# Sheet_TCU.net
KiCad netlist of a schematic drawn in Altium Designer
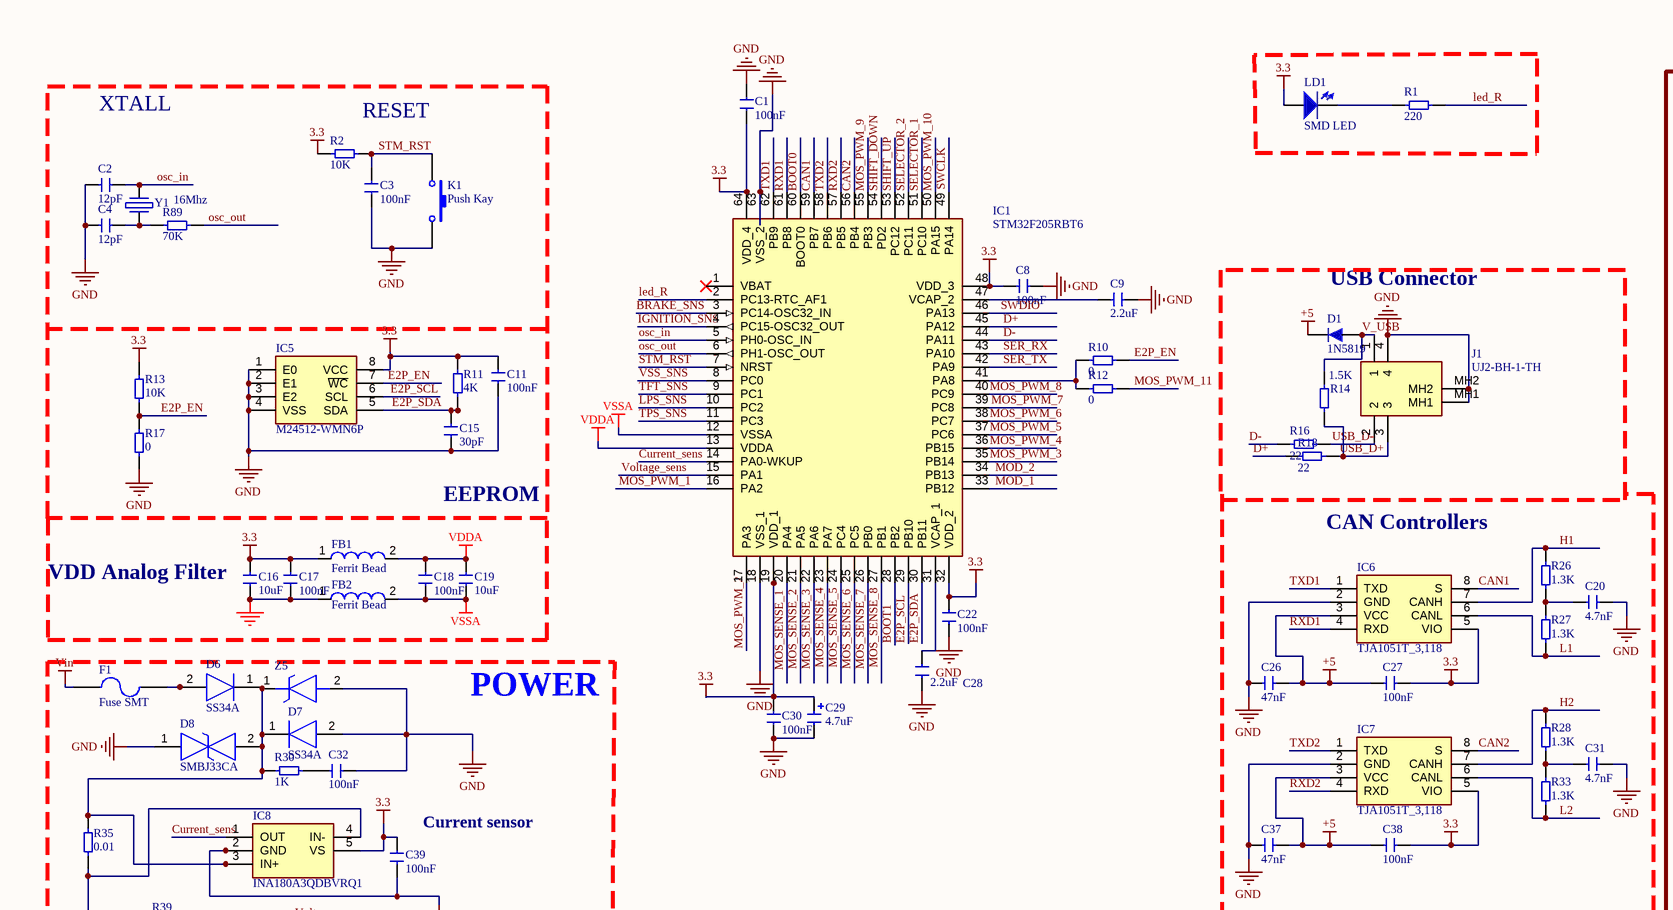
[diagram p0: Sheet_TCU.SchDoc, top left]
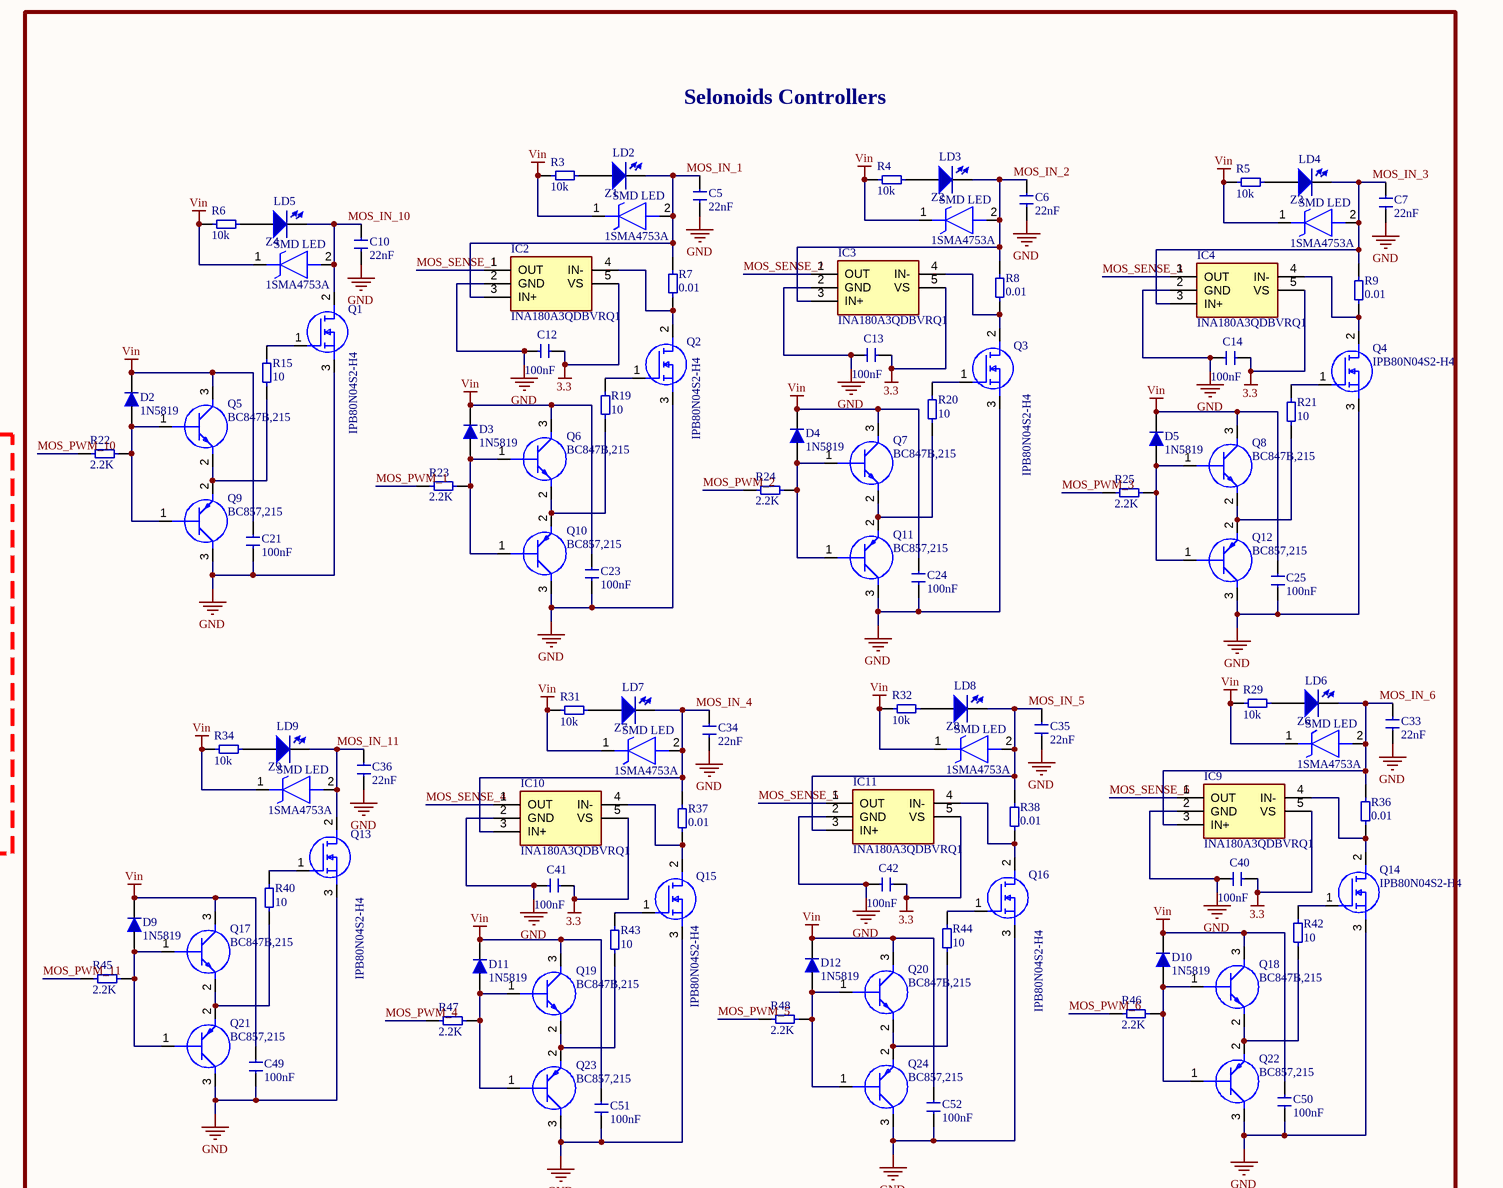
[diagram p1: Sheet_TCU.SchDoc, top right]
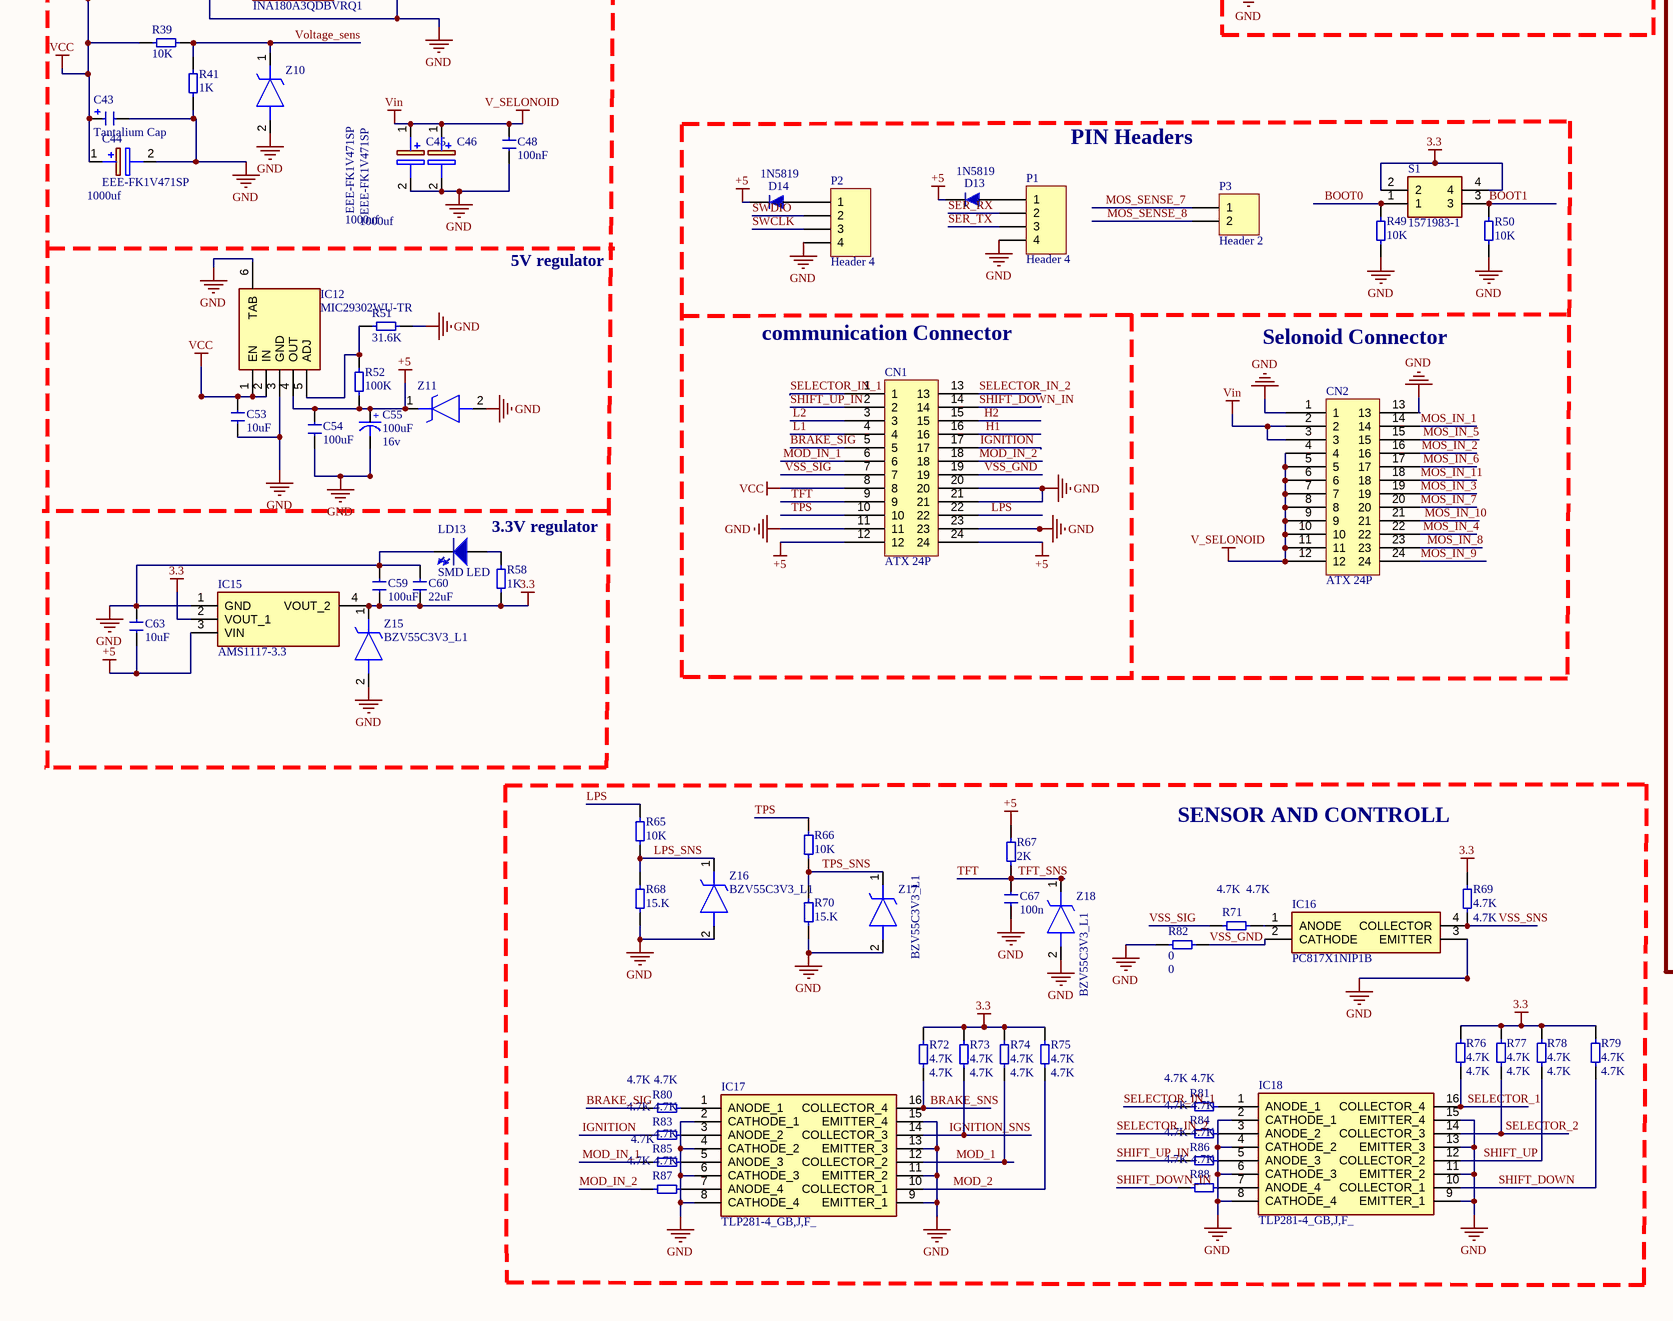
[diagram p2: Sheet_TCU.SchDoc, bottom left]
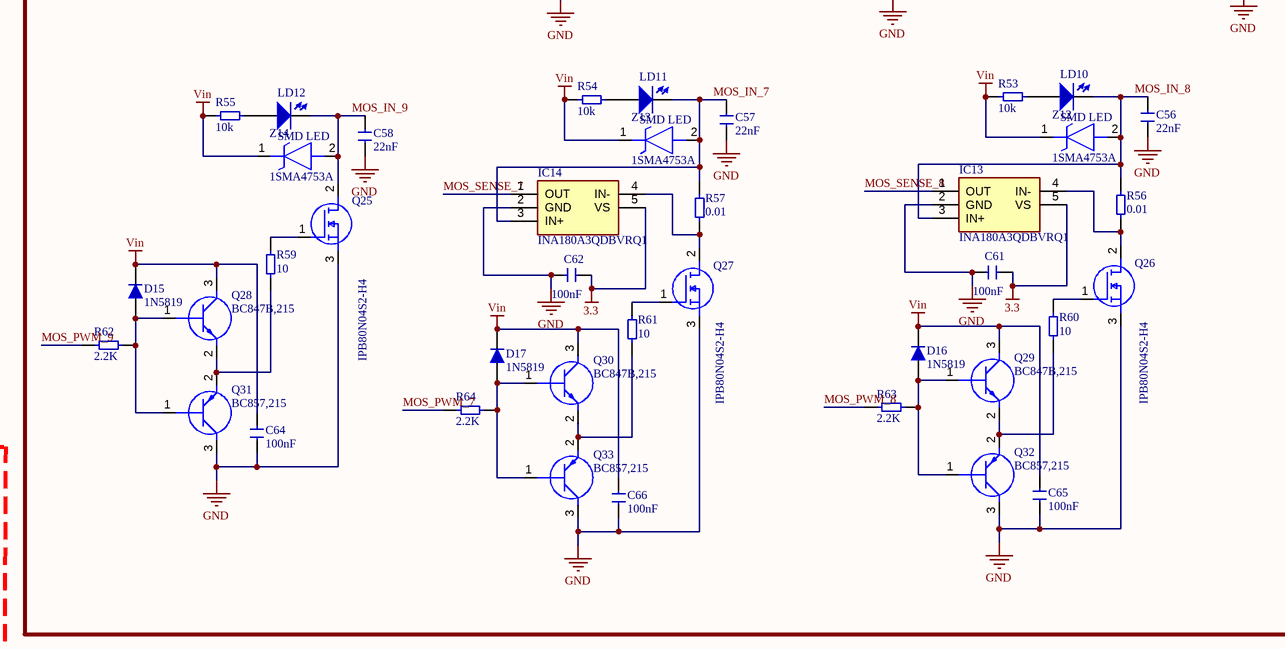
[diagram p3: Sheet_TCU.SchDoc, bottom right]

(export (version "E")
  (design (tool "Eeschema 10.0.6"))
  (components
    (comp (ref "C1")
      (value "100nF")
      (footprint "0402 Capacitor")
      (fields (field (name "Comment") "Capacitor SMD"))
      (libsource (lib "ZetaBoard_Lib") (part "Capacitor SMD"))
    )
    (comp (ref "C2")
      (value "12pF")
      (footprint "0402 Capacitor")
      (fields (field (name "Comment") "Capacitor SMD"))
      (libsource (lib "ZetaBoard_Lib") (part "Capacitor SMD"))
    )
    (comp (ref "C3")
      (value "100nF")
      (footprint "0402 Capacitor")
      (fields (field (name "Comment") "Capacitor SMD"))
      (libsource (lib "ZetaBoard_Lib") (part "Capacitor SMD"))
    )
    (comp (ref "C4")
      (value "12pF")
      (footprint "0402 Capacitor")
      (fields (field (name "Comment") "Capacitor SMD"))
      (libsource (lib "ZetaBoard_Lib") (part "Capacitor SMD"))
    )
    (comp (ref "C5")
      (value "22nF")
      (footprint "0402 Capacitor")
      (fields (field (name "Comment") "Capacitor SMD"))
      (libsource (lib "ZetaBoard_Lib") (part "Capacitor SMD"))
    )
    (comp (ref "C6")
      (value "22nF")
      (footprint "0402 Capacitor")
      (fields (field (name "Comment") "Capacitor SMD"))
      (libsource (lib "ZetaBoard_Lib") (part "Capacitor SMD"))
    )
    (comp (ref "C7")
      (value "22nF")
      (footprint "0402 Capacitor")
      (fields (field (name "Comment") "Capacitor SMD"))
      (libsource (lib "ZetaBoard_Lib") (part "Capacitor SMD"))
    )
    (comp (ref "C8")
      (value "100nF")
      (footprint "0402 Capacitor")
      (fields (field (name "Comment") "Capacitor SMD"))
      (libsource (lib "ZetaBoard_Lib") (part "Capacitor SMD"))
    )
    (comp (ref "C9")
      (value "2.2uF")
      (footprint "0402 Capacitor")
      (fields (field (name "Comment") "Capacitor SMD"))
      (libsource (lib "ZetaBoard_Lib") (part "Capacitor SMD"))
    )
    (comp (ref "C10")
      (value "22nF")
      (footprint "0402 Capacitor")
      (fields (field (name "Comment") "Capacitor SMD"))
      (libsource (lib "ZetaBoard_Lib") (part "Capacitor SMD"))
    )
    (comp (ref "C11")
      (value "100nF")
      (footprint "0402 Capacitor")
      (fields (field (name "Comment") "Capacitor SMD"))
      (libsource (lib "ZetaBoard_Lib") (part "Capacitor SMD"))
    )
    (comp (ref "C12")
      (value "100nF")
      (footprint "0402 Capacitor")
      (fields (field (name "Comment") "Capacitor SMD"))
      (libsource (lib "ZetaBoard_Lib") (part "Capacitor SMD"))
    )
    (comp (ref "C13")
      (value "100nF")
      (footprint "0402 Capacitor")
      (fields (field (name "Comment") "Capacitor SMD"))
      (libsource (lib "ZetaBoard_Lib") (part "Capacitor SMD"))
    )
    (comp (ref "C14")
      (value "100nF")
      (footprint "0402 Capacitor")
      (fields (field (name "Comment") "Capacitor SMD"))
      (libsource (lib "ZetaBoard_Lib") (part "Capacitor SMD"))
    )
    (comp (ref "C15")
      (value "30pF")
      (footprint "0402 Capacitor")
      (fields (field (name "Comment") "Capacitor SMD"))
      (libsource (lib "ZetaBoard_Lib") (part "Capacitor SMD"))
    )
    (comp (ref "C16")
      (value "10uF")
      (footprint "0603 Capacitor")
      (fields (field (name "Comment") "Capacitor SMD"))
      (libsource (lib "ZetaBoard_Lib") (part "Capacitor SMD"))
    )
    (comp (ref "C17")
      (value "100nF")
      (footprint "0402 Capacitor")
      (fields (field (name "Comment") "Capacitor SMD"))
      (libsource (lib "ZetaBoard_Lib") (part "Capacitor SMD"))
    )
    (comp (ref "C18")
      (value "100nF")
      (footprint "0402 Capacitor")
      (fields (field (name "Comment") "Capacitor SMD"))
      (libsource (lib "ZetaBoard_Lib") (part "Capacitor SMD"))
    )
    (comp (ref "C19")
      (value "10uF")
      (footprint "0603 Capacitor")
      (fields (field (name "Comment") "Capacitor SMD"))
      (libsource (lib "ZetaBoard_Lib") (part "Capacitor SMD"))
    )
    (comp (ref "C20")
      (value "4.7nF")
      (footprint "0402 Capacitor")
      (fields (field (name "Comment") "Capacitor SMD"))
      (libsource (lib "ZetaBoard_Lib") (part "Capacitor SMD"))
    )
    (comp (ref "C21")
      (value "100nF")
      (footprint "0402 Capacitor")
      (fields (field (name "Comment") "Capacitor SMD"))
      (libsource (lib "ZetaBoard_Lib") (part "Capacitor SMD"))
    )
    (comp (ref "C22")
      (value "100nF")
      (footprint "0402 Capacitor")
      (fields (field (name "Comment") "Capacitor SMD"))
      (libsource (lib "ZetaBoard_Lib") (part "Capacitor SMD"))
    )
    (comp (ref "C23")
      (value "100nF")
      (footprint "0402 Capacitor")
      (fields (field (name "Comment") "Capacitor SMD"))
      (libsource (lib "ZetaBoard_Lib") (part "Capacitor SMD"))
    )
    (comp (ref "C24")
      (value "100nF")
      (footprint "0402 Capacitor")
      (fields (field (name "Comment") "Capacitor SMD"))
      (libsource (lib "ZetaBoard_Lib") (part "Capacitor SMD"))
    )
    (comp (ref "C25")
      (value "100nF")
      (footprint "0402 Capacitor")
      (fields (field (name "Comment") "Capacitor SMD"))
      (libsource (lib "ZetaBoard_Lib") (part "Capacitor SMD"))
    )
    (comp (ref "C26")
      (value "47nF")
      (footprint "0402 Capacitor")
      (fields (field (name "Comment") "Capacitor SMD"))
      (libsource (lib "ZetaBoard_Lib") (part "Capacitor SMD"))
    )
    (comp (ref "C27")
      (value "100nF")
      (footprint "0402 Capacitor")
      (fields (field (name "Comment") "Capacitor SMD"))
      (libsource (lib "ZetaBoard_Lib") (part "Capacitor SMD"))
    )
    (comp (ref "C28")
      (value "2.2uF")
      (footprint "0402 Capacitor")
      (fields (field (name "Comment") "Capacitor SMD"))
      (libsource (lib "ZetaBoard_Lib") (part "Capacitor SMD"))
    )
    (comp (ref "C29")
      (value "4.7uF")
      (footprint "Tantalium Size A")
      (libsource (lib "ZetaBoard_Lib") (part "Capacitor Tantalium"))
    )
    (comp (ref "C30")
      (value "100nF")
      (footprint "0402 Capacitor")
      (fields (field (name "Comment") "Capacitor SMD"))
      (libsource (lib "ZetaBoard_Lib") (part "Capacitor SMD"))
    )
    (comp (ref "C31")
      (value "4.7nF")
      (footprint "0402 Capacitor")
      (fields (field (name "Comment") "Capacitor SMD"))
      (libsource (lib "ZetaBoard_Lib") (part "Capacitor SMD"))
    )
    (comp (ref "C32")
      (value "100nF")
      (footprint "0805 Capacitor")
      (fields (field (name "Comment") "Capacitor SMD"))
      (libsource (lib "ZetaBoard_Lib") (part "Capacitor SMD"))
    )
    (comp (ref "C33")
      (value "22nF")
      (footprint "0402 Capacitor")
      (fields (field (name "Comment") "Capacitor SMD"))
      (libsource (lib "ZetaBoard_Lib") (part "Capacitor SMD"))
    )
    (comp (ref "C34")
      (value "22nF")
      (footprint "0402 Capacitor")
      (fields (field (name "Comment") "Capacitor SMD"))
      (libsource (lib "ZetaBoard_Lib") (part "Capacitor SMD"))
    )
    (comp (ref "C35")
      (value "22nF")
      (footprint "0402 Capacitor")
      (fields (field (name "Comment") "Capacitor SMD"))
      (libsource (lib "ZetaBoard_Lib") (part "Capacitor SMD"))
    )
    (comp (ref "C36")
      (value "22nF")
      (footprint "0402 Capacitor")
      (fields (field (name "Comment") "Capacitor SMD"))
      (libsource (lib "ZetaBoard_Lib") (part "Capacitor SMD"))
    )
    (comp (ref "C37")
      (value "47nF")
      (footprint "0402 Capacitor")
      (fields (field (name "Comment") "Capacitor SMD"))
      (libsource (lib "ZetaBoard_Lib") (part "Capacitor SMD"))
    )
    (comp (ref "C38")
      (value "100nF")
      (footprint "0402 Capacitor")
      (fields (field (name "Comment") "Capacitor SMD"))
      (libsource (lib "ZetaBoard_Lib") (part "Capacitor SMD"))
    )
    (comp (ref "C39")
      (value "100nF")
      (footprint "0402 Capacitor")
      (fields (field (name "Comment") "Capacitor SMD"))
      (libsource (lib "ZetaBoard_Lib") (part "Capacitor SMD"))
    )
    (comp (ref "C40")
      (value "100nF")
      (footprint "0402 Capacitor")
      (fields (field (name "Comment") "Capacitor SMD"))
      (libsource (lib "ZetaBoard_Lib") (part "Capacitor SMD"))
    )
    (comp (ref "C41")
      (value "100nF")
      (footprint "0402 Capacitor")
      (fields (field (name "Comment") "Capacitor SMD"))
      (libsource (lib "ZetaBoard_Lib") (part "Capacitor SMD"))
    )
    (comp (ref "C42")
      (value "100nF")
      (footprint "0402 Capacitor")
      (fields (field (name "Comment") "Capacitor SMD"))
      (libsource (lib "ZetaBoard_Lib") (part "Capacitor SMD"))
    )
    (comp (ref "C43")
      (value "Tantalium Cap")
      (footprint "Tantalium Size A")
      (description "100nF")
      (libsource (lib "ZetaBoard_Lib") (part "Capacitor Tantalium"))
    )
    (comp (ref "C44")
      (value "EEE-FK1V471SP")
      (footprint "SamacSys:CAPAE1030X1050N")
      (description "Capacitor Polarised")
      (fields (field (name "MOUSER PART NUMBER") "667-EEE-FK1V471SP") (field (name "ALTIUM_VALUE") "1000uf"))
      (libsource (lib "") (part "EEE-FK1V471SP_1"))
    )
    (comp (ref "C45")
      (value "EEE-FK1V471SP")
      (footprint "SamacSys:CAPAE1030X1050N")
      (description "Capacitor Polarised")
      (fields (field (name "MOUSER PART NUMBER") "667-EEE-FK1V471SP") (field (name "ALTIUM_VALUE") "1000uf"))
      (libsource (lib "SamacSys") (part "EEE-FK1V471SP"))
    )
    (comp (ref "C46")
      (value "EEE-FK1V471SP")
      (footprint "SamacSys:CAPAE1030X1050N")
      (description "Capacitor Polarised")
      (fields (field (name "MOUSER PART NUMBER") "667-EEE-FK1V471SP") (field (name "ALTIUM_VALUE") "1000uf"))
      (libsource (lib "SamacSys") (part "EEE-FK1V471SP"))
    )
    (comp (ref "C48")
      (value "100nF")
      (footprint "0805 Capacitor")
      (fields (field (name "Comment") "Capacitor SMD"))
      (libsource (lib "ZetaBoard_Lib") (part "Capacitor SMD"))
    )
    (comp (ref "C49")
      (value "100nF")
      (footprint "0402 Capacitor")
      (fields (field (name "Comment") "Capacitor SMD"))
      (libsource (lib "ZetaBoard_Lib") (part "Capacitor SMD"))
    )
    (comp (ref "C50")
      (value "100nF")
      (footprint "0402 Capacitor")
      (fields (field (name "Comment") "Capacitor SMD"))
      (libsource (lib "ZetaBoard_Lib") (part "Capacitor SMD"))
    )
    (comp (ref "C51")
      (value "100nF")
      (footprint "0402 Capacitor")
      (fields (field (name "Comment") "Capacitor SMD"))
      (libsource (lib "ZetaBoard_Lib") (part "Capacitor SMD"))
    )
    (comp (ref "C52")
      (value "100nF")
      (footprint "0402 Capacitor")
      (fields (field (name "Comment") "Capacitor SMD"))
      (libsource (lib "ZetaBoard_Lib") (part "Capacitor SMD"))
    )
    (comp (ref "C53")
      (value "10uF")
      (footprint "0603 Capacitor")
      (fields (field (name "Comment") "Capacitor SMD"))
      (libsource (lib "ZetaBoard_Lib") (part "Capacitor SMD"))
    )
    (comp (ref "C54")
      (value "100uF")
      (footprint "0805 Capacitor")
      (fields (field (name "Comment") "Capacitor SMD"))
      (libsource (lib "ZetaBoard_Lib") (part "Capacitor SMD"))
    )
    (comp (ref "C55")
      (value "Capacitor Aluminum Electrolytic SMD")
      (footprint "Capacitor Aluminum 6.3x7.7")
      (fields (field (name "ALTIUM_UNNAMED_1") "100uF") (field (name "ALTIUM_UNNAMED_2") "16v"))
      (libsource (lib "ZetaBoard_Lib") (part "Capacitor Aluminum Electrolytic SMD"))
    )
    (comp (ref "C56")
      (value "22nF")
      (footprint "0402 Capacitor")
      (fields (field (name "Comment") "Capacitor SMD"))
      (libsource (lib "ZetaBoard_Lib") (part "Capacitor SMD"))
    )
    (comp (ref "C57")
      (value "22nF")
      (footprint "0402 Capacitor")
      (fields (field (name "Comment") "Capacitor SMD"))
      (libsource (lib "ZetaBoard_Lib") (part "Capacitor SMD"))
    )
    (comp (ref "C58")
      (value "22nF")
      (footprint "0402 Capacitor")
      (fields (field (name "Comment") "Capacitor SMD"))
      (libsource (lib "ZetaBoard_Lib") (part "Capacitor SMD"))
    )
    (comp (ref "C59")
      (value "100uF")
      (footprint "0805 Capacitor")
      (fields (field (name "Comment") "Capacitor SMD"))
      (libsource (lib "ZetaBoard_Lib") (part "Capacitor SMD"))
    )
    (comp (ref "C60")
      (value "22uF")
      (footprint "0603 Capacitor")
      (fields (field (name "Comment") "Capacitor SMD"))
      (libsource (lib "ZetaBoard_Lib") (part "Capacitor SMD"))
    )
    (comp (ref "C61")
      (value "100nF")
      (footprint "0402 Capacitor")
      (fields (field (name "Comment") "Capacitor SMD"))
      (libsource (lib "ZetaBoard_Lib") (part "Capacitor SMD"))
    )
    (comp (ref "C62")
      (value "100nF")
      (footprint "0402 Capacitor")
      (fields (field (name "Comment") "Capacitor SMD"))
      (libsource (lib "ZetaBoard_Lib") (part "Capacitor SMD"))
    )
    (comp (ref "C63")
      (value "10uF")
      (footprint "0603 Capacitor")
      (fields (field (name "Comment") "Capacitor SMD"))
      (libsource (lib "ZetaBoard_Lib") (part "Capacitor SMD"))
    )
    (comp (ref "C64")
      (value "100nF")
      (footprint "0402 Capacitor")
      (fields (field (name "Comment") "Capacitor SMD"))
      (libsource (lib "ZetaBoard_Lib") (part "Capacitor SMD"))
    )
    (comp (ref "C65")
      (value "100nF")
      (footprint "0402 Capacitor")
      (fields (field (name "Comment") "Capacitor SMD"))
      (libsource (lib "ZetaBoard_Lib") (part "Capacitor SMD"))
    )
    (comp (ref "C66")
      (value "100nF")
      (footprint "0402 Capacitor")
      (fields (field (name "Comment") "Capacitor SMD"))
      (libsource (lib "ZetaBoard_Lib") (part "Capacitor SMD"))
    )
    (comp (ref "C67")
      (value "100n")
      (footprint "0603 Capacitor")
      (fields (field (name "Comment") "Capacitor SMD"))
      (libsource (lib "ZetaBoard_Lib") (part "Capacitor SMD"))
    )
    (comp (ref "CN1")
      (value "ATX 24P")
      (footprint "ATX 24P")
      (libsource (lib "ZetaBoard_Lib") (part "ATX 24P"))
    )
    (comp (ref "CN2")
      (value "ATX 24P")
      (footprint "ATX 24P")
      (libsource (lib "ZetaBoard_Lib") (part "ATX 24P"))
    )
    (comp (ref "D1")
      (value "1N5819")
      (footprint "DO-214AC(SMA)")
      (libsource (lib "ZetaBoard_Lib") (part "1N5819(SS14)"))
    )
    (comp (ref "D2")
      (value "1N5819")
      (footprint "DO-214AC(SMA)")
      (libsource (lib "ZetaBoard_Lib") (part "1N5819(SS14)"))
    )
    (comp (ref "D3")
      (value "1N5819")
      (footprint "DO-214AC(SMA)")
      (libsource (lib "ZetaBoard_Lib") (part "1N5819(SS14)"))
    )
    (comp (ref "D4")
      (value "1N5819")
      (footprint "DO-214AC(SMA)")
      (libsource (lib "ZetaBoard_Lib") (part "1N5819(SS14)"))
    )
    (comp (ref "D5")
      (value "1N5819")
      (footprint "DO-214AC(SMA)")
      (libsource (lib "ZetaBoard_Lib") (part "1N5819(SS14)"))
    )
    (comp (ref "D6")
      (value "SS34A")
      (footprint "SamacSys:DIOM5026X262N")
      (description "Diode")
      (libsource (lib "SamacSys") (part "SS34A"))
    )
    (comp (ref "D7")
      (value "SS34A")
      (footprint "SamacSys:DIOM5026X262N")
      (description "Diode")
      (libsource (lib "SamacSys") (part "SS34A"))
    )
    (comp (ref "D8")
      (value "SMBJ33CA")
      (footprint "SamacSys:DIONM5336X265N")
      (description "TVS Diode (Bi-directional)")
      (fields (field (name "MOUSER PART NUMBER") "821-SMBJ33CA"))
      (libsource (lib "SamacSys") (part "SMBJ33CA"))
    )
    (comp (ref "D9")
      (value "1N5819")
      (footprint "DO-214AC(SMA)")
      (libsource (lib "ZetaBoard_Lib") (part "1N5819(SS14)"))
    )
    (comp (ref "D10")
      (value "1N5819")
      (footprint "DO-214AC(SMA)")
      (libsource (lib "ZetaBoard_Lib") (part "1N5819(SS14)"))
    )
    (comp (ref "D11")
      (value "1N5819")
      (footprint "DO-214AC(SMA)")
      (libsource (lib "ZetaBoard_Lib") (part "1N5819(SS14)"))
    )
    (comp (ref "D12")
      (value "1N5819")
      (footprint "DO-214AC(SMA)")
      (libsource (lib "ZetaBoard_Lib") (part "1N5819(SS14)"))
    )
    (comp (ref "D13")
      (value "1N5819")
      (footprint "DO-214AC(SMA)")
      (libsource (lib "ZetaBoard_Lib") (part "1N5819(SS14)"))
    )
    (comp (ref "D14")
      (value "1N5819")
      (footprint "DO-214AC(SMA)")
      (libsource (lib "ZetaBoard_Lib") (part "1N5819(SS14)"))
    )
    (comp (ref "D15")
      (value "1N5819")
      (footprint "DO-214AC(SMA)")
      (libsource (lib "ZetaBoard_Lib") (part "1N5819(SS14)"))
    )
    (comp (ref "D16")
      (value "1N5819")
      (footprint "DO-214AC(SMA)")
      (libsource (lib "ZetaBoard_Lib") (part "1N5819(SS14)"))
    )
    (comp (ref "D17")
      (value "1N5819")
      (footprint "DO-214AC(SMA)")
      (libsource (lib "ZetaBoard_Lib") (part "1N5819(SS14)"))
    )
    (comp (ref "F1")
      (value "Fuse SMT")
      (footprint "1812 Fuse")
      (libsource (lib "ZetaBoard_Lib") (part "Fuse SMT"))
    )
    (comp (ref "FB1")
      (value "Ferrit Bead")
      (footprint "0805 Ferrit Bead")
      (libsource (lib "ZetaBoard_Lib") (part "Ferrit Bead"))
    )
    (comp (ref "FB2")
      (value "Ferrit Bead")
      (footprint "0805 Ferrit Bead")
      (libsource (lib "ZetaBoard_Lib") (part "Ferrit Bead"))
    )
    (comp (ref "IC1")
      (value "STM32F205RBT6")
      (footprint "SamacSys:QFP50P1200X1200X160-64N")
      (description "Integrated Circuit")
      (fields (field (name "MOUSER PART NUMBER") "511-STM32F205RBT6"))
      (libsource (lib "SamacSys") (part "STM32F205RBT6"))
    )
    (comp (ref "IC2")
      (value "INA180A3QDBVRQ1")
      (footprint "SOT95P280X145-5N")
      (description "Integrated Circuit")
      (fields (field (name "MOUSER PART NUMBER") "595-INA180A3QDBVRQ1"))
      (libsource (lib "SamacSys") (part "INA180A3QDBVRQ1"))
    )
    (comp (ref "IC3")
      (value "INA180A3QDBVRQ1")
      (footprint "SOT95P280X145-5N")
      (description "Integrated Circuit")
      (fields (field (name "MOUSER PART NUMBER") "595-INA180A3QDBVRQ1"))
      (libsource (lib "SamacSys") (part "INA180A3QDBVRQ1"))
    )
    (comp (ref "IC4")
      (value "INA180A3QDBVRQ1")
      (footprint "SOT95P280X145-5N")
      (description "Integrated Circuit")
      (fields (field (name "MOUSER PART NUMBER") "595-INA180A3QDBVRQ1"))
      (libsource (lib "SamacSys") (part "INA180A3QDBVRQ1"))
    )
    (comp (ref "IC5")
      (value "M24512-WMN6P")
      (footprint "SamacSys:SOIC127P600X175-8N")
      (description "Integrated Circuit")
      (fields (field (name "MOUSER PART NUMBER") "511-M24512-WMN6P"))
      (libsource (lib "SamacSys") (part "M24512-WMN6P"))
    )
    (comp (ref "IC6")
      (value "TJA1051T_3,118")
      (footprint "SOIC127P600X175-8N")
      (description "Integrated Circuit")
      (fields
        (field (name "MANUFACTURER_PART_NUMBER") "TJA1051T/3,118")
        (field (name "MOUSER PART NUMBER") "771-TJA1051T3118")
      )
      (libsource (lib "SamacSys") (part "TJA1051T_3,118"))
    )
    (comp (ref "IC7")
      (value "TJA1051T_3,118")
      (footprint "SOIC127P600X175-8N")
      (description "Integrated Circuit")
      (fields
        (field (name "MANUFACTURER_PART_NUMBER") "TJA1051T/3,118")
        (field (name "MOUSER PART NUMBER") "771-TJA1051T3118")
      )
      (libsource (lib "SamacSys") (part "TJA1051T_3,118"))
    )
    (comp (ref "IC8")
      (value "INA180A3QDBVRQ1")
      (footprint "SamacSys:SOT95P280X145-5N")
      (description "Integrated Circuit")
      (fields (field (name "MOUSER PART NUMBER") "595-INA180A3QDBVRQ1"))
      (libsource (lib "*") (part "INA180A3QDBVRQ1"))
    )
    (comp (ref "IC9")
      (value "INA180A3QDBVRQ1")
      (footprint "SOT95P280X145-5N")
      (description "Integrated Circuit")
      (fields (field (name "MOUSER PART NUMBER") "595-INA180A3QDBVRQ1"))
      (libsource (lib "SamacSys") (part "INA180A3QDBVRQ1"))
    )
    (comp (ref "IC10")
      (value "INA180A3QDBVRQ1")
      (footprint "SOT95P280X145-5N")
      (description "Integrated Circuit")
      (fields (field (name "MOUSER PART NUMBER") "595-INA180A3QDBVRQ1"))
      (libsource (lib "SamacSys") (part "INA180A3QDBVRQ1"))
    )
    (comp (ref "IC11")
      (value "INA180A3QDBVRQ1")
      (footprint "SOT95P280X145-5N")
      (description "Integrated Circuit")
      (fields (field (name "MOUSER PART NUMBER") "595-INA180A3QDBVRQ1"))
      (libsource (lib "SamacSys") (part "INA180A3QDBVRQ1"))
    )
    (comp (ref "IC12")
      (value "MIC29302WU-TR")
      (footprint "MIC29302WUTR")
      (description "Integrated Circuit")
      (fields (field (name "MOUSER PART NUMBER") "998-MIC29302WUTR"))
      (libsource (lib "SamacSys") (part "MIC29302WU-TR"))
    )
    (comp (ref "IC13")
      (value "INA180A3QDBVRQ1")
      (footprint "SOT95P280X145-5N")
      (description "Integrated Circuit")
      (fields (field (name "MOUSER PART NUMBER") "595-INA180A3QDBVRQ1"))
      (libsource (lib "SamacSys") (part "INA180A3QDBVRQ1"))
    )
    (comp (ref "IC14")
      (value "INA180A3QDBVRQ1")
      (footprint "SOT95P280X145-5N")
      (description "Integrated Circuit")
      (fields (field (name "MOUSER PART NUMBER") "595-INA180A3QDBVRQ1"))
      (libsource (lib "SamacSys") (part "INA180A3QDBVRQ1"))
    )
    (comp (ref "IC15")
      (value "AMS1117-3.3")
      (footprint "SamacSys:SOT 223-4")
      (description "Integrated Circuit")
      (libsource (lib "SamacSys") (part "AMS1117-3.3"))
    )
    (comp (ref "IC16")
      (value "PC817X1NIP1B")
      (footprint "SamacSys:SOP254P960X420-4N")
      (description "Integrated Circuit")
      (fields (field (name "MOUSER PART NUMBER") "852-PC817X1NIP1B"))
      (libsource (lib "SamacSys") (part "PC817X1NIP1B"))
    )
    (comp (ref "IC17")
      (value "TLP281-4_GB,J,F_")
      (footprint "SamacSys:SOIC127P700X210-16N")
      (description "Integrated Circuit")
      (fields
        (field (name "MANUFACTURER_PART_NUMBER") "TLP281-4(GB,J,F)")
        (field (name "MOUSER PART NUMBER") "757-TLP281-4(GB,J,F)")
      )
      (libsource (lib "SamacSys") (part "TLP281-4_GB,J,F_"))
    )
    (comp (ref "IC18")
      (value "TLP281-4_GB,J,F_")
      (footprint "SamacSys:SOIC127P700X210-16N")
      (description "Integrated Circuit")
      (fields
        (field (name "MANUFACTURER_PART_NUMBER") "TLP281-4(GB,J,F)")
        (field (name "MOUSER PART NUMBER") "757-TLP281-4(GB,J,F)")
      )
      (libsource (lib "SamacSys") (part "TLP281-4_GB,J,F_"))
    )
    (comp (ref "J1")
      (value "UJ2-BH-1-TH")
      (footprint "UJ2BH1TH")
      (description "Connector")
      (fields (field (name "MOUSER PART NUMBER") "490-UJ2-BH-1-TH"))
      (libsource (lib "SamacSys") (part "UJ2-BH-1-TH"))
    )
    (comp (ref "K1")
      (value "Push Kay")
      (footprint "SW_KFC")
      (libsource (lib "ZetaBoard_Lib") (part "Push Kay"))
    )
    (comp (ref "LD1")
      (value "SMD LED")
      (footprint "LED_0603 R")
      (libsource (lib "ZetaBoard_Lib") (part "LED SMD"))
    )
    (comp (ref "LD2")
      (value "SMD LED")
      (footprint "LED_0603 B")
      (libsource (lib "ZetaBoard_Lib") (part "LED SMD"))
    )
    (comp (ref "LD3")
      (value "SMD LED")
      (footprint "LED_0603 B")
      (libsource (lib "ZetaBoard_Lib") (part "LED SMD"))
    )
    (comp (ref "LD4")
      (value "SMD LED")
      (footprint "LED_0603 B")
      (libsource (lib "ZetaBoard_Lib") (part "LED SMD"))
    )
    (comp (ref "LD5")
      (value "SMD LED")
      (footprint "LED_0603 B")
      (libsource (lib "ZetaBoard_Lib") (part "LED SMD"))
    )
    (comp (ref "LD6")
      (value "SMD LED")
      (footprint "LED_0603 B")
      (libsource (lib "ZetaBoard_Lib") (part "LED SMD"))
    )
    (comp (ref "LD7")
      (value "SMD LED")
      (footprint "LED_0603 B")
      (libsource (lib "ZetaBoard_Lib") (part "LED SMD"))
    )
    (comp (ref "LD8")
      (value "SMD LED")
      (footprint "LED_0603 B")
      (libsource (lib "ZetaBoard_Lib") (part "LED SMD"))
    )
    (comp (ref "LD9")
      (value "SMD LED")
      (footprint "LED_0603 B")
      (libsource (lib "ZetaBoard_Lib") (part "LED SMD"))
    )
    (comp (ref "LD10")
      (value "SMD LED")
      (footprint "LED_0603 B")
      (libsource (lib "ZetaBoard_Lib") (part "LED SMD"))
    )
    (comp (ref "LD11")
      (value "SMD LED")
      (footprint "LED_0603 B")
      (libsource (lib "ZetaBoard_Lib") (part "LED SMD"))
    )
    (comp (ref "LD12")
      (value "SMD LED")
      (footprint "LED_0603 B")
      (libsource (lib "ZetaBoard_Lib") (part "LED SMD"))
    )
    (comp (ref "LD13")
      (value "SMD LED")
      (footprint "LED_0603 R")
      (libsource (lib "ZetaBoard_Lib") (part "LED SMD"))
    )
    (comp (ref "P1")
      (value "Header 4")
      (footprint "HDR1X4")
      (description "Header, 4-Pin")
      (fields (field (name "PUBLISHER") "Altium Limited"))
      (libsource (lib "Miscellaneous Connectors") (part "Header 4"))
    )
    (comp (ref "P2")
      (value "Header 4")
      (footprint "HDR1X4")
      (description "Header, 4-Pin")
      (fields (field (name "PUBLISHER") "Altium Limited"))
      (libsource (lib "Miscellaneous Connectors") (part "Header 4"))
    )
    (comp (ref "P3")
      (value "Header 2")
      (footprint "HDR1X2")
      (description "Header, 2-Pin")
      (fields (field (name "PUBLISHER") "Altium Limited"))
      (libsource (lib "Miscellaneous Connectors") (part "Header 2"))
    )
    (comp (ref "Q1")
      (value "IPB80N04S2-H4")
      (footprint "IRF2804STRLPBF")
      (description "MOSFET (N-Channel)")
      (fields
        (field (name "MANUFACTURER_PART_NUMBER") "IRF1010NSPBF")
        (field (name "MOUSER PART NUMBER") "942-IRF1010NSPBF")
      )
      (libsource (lib "SamacSys") (part "IRF1010NSPBF"))
    )
    (comp (ref "Q2")
      (value "IPB80N04S2-H4")
      (footprint "IRF2804STRLPBF")
      (description "MOSFET (N-Channel)")
      (fields
        (field (name "MANUFACTURER_PART_NUMBER") "IRF1010NSPBF")
        (field (name "MOUSER PART NUMBER") "942-IRF1010NSPBF")
      )
      (libsource (lib "SamacSys") (part "IRF1010NSPBF"))
    )
    (comp (ref "Q3")
      (value "IPB80N04S2-H4")
      (footprint "IRF2804STRLPBF")
      (description "MOSFET (N-Channel)")
      (fields
        (field (name "MANUFACTURER_PART_NUMBER") "IRF1010NSPBF")
        (field (name "MOUSER PART NUMBER") "942-IRF1010NSPBF")
      )
      (libsource (lib "SamacSys") (part "IRF1010NSPBF"))
    )
    (comp (ref "Q4")
      (value "IPB80N04S2-H4")
      (footprint "IRF2804STRLPBF")
      (description "MOSFET (N-Channel)")
      (fields
        (field (name "MANUFACTURER_PART_NUMBER") "IRF1010NSPBF")
        (field (name "MOUSER PART NUMBER") "942-IRF1010NSPBF")
      )
      (libsource (lib "SamacSys") (part "IRF1010NSPBF"))
    )
    (comp (ref "Q5")
      (value "BC847B,215")
      (footprint "BC847B215")
      (description "Transistor BJT NPN")
      (fields (field (name "MOUSER PART NUMBER") "771-BC847B-T/R"))
      (libsource (lib "SamacSys") (part "BC847B,215"))
    )
    (comp (ref "Q6")
      (value "BC847B,215")
      (footprint "BC847B215")
      (description "Transistor BJT NPN")
      (fields (field (name "MOUSER PART NUMBER") "771-BC847B-T/R"))
      (libsource (lib "SamacSys") (part "BC847B,215"))
    )
    (comp (ref "Q7")
      (value "BC847B,215")
      (footprint "BC847B215")
      (description "Transistor BJT NPN")
      (fields (field (name "MOUSER PART NUMBER") "771-BC847B-T/R"))
      (libsource (lib "SamacSys") (part "BC847B,215"))
    )
    (comp (ref "Q8")
      (value "BC847B,215")
      (footprint "BC847B215")
      (description "Transistor BJT NPN")
      (fields (field (name "MOUSER PART NUMBER") "771-BC847B-T/R"))
      (libsource (lib "SamacSys") (part "BC847B,215"))
    )
    (comp (ref "Q9")
      (value "BC857,215")
      (footprint "BC857215")
      (description "Transistor BJT PNP")
      (fields (field (name "MOUSER PART NUMBER") "771-BC857215"))
      (libsource (lib "SamacSys") (part "BC857,215"))
    )
    (comp (ref "Q10")
      (value "BC857,215")
      (footprint "BC857215")
      (description "Transistor BJT PNP")
      (fields (field (name "MOUSER PART NUMBER") "771-BC857215"))
      (libsource (lib "SamacSys") (part "BC857,215"))
    )
    (comp (ref "Q11")
      (value "BC857,215")
      (footprint "BC857215")
      (description "Transistor BJT PNP")
      (fields (field (name "MOUSER PART NUMBER") "771-BC857215"))
      (libsource (lib "SamacSys") (part "BC857,215"))
    )
    (comp (ref "Q12")
      (value "BC857,215")
      (footprint "BC857215")
      (description "Transistor BJT PNP")
      (fields (field (name "MOUSER PART NUMBER") "771-BC857215"))
      (libsource (lib "SamacSys") (part "BC857,215"))
    )
    (comp (ref "Q13")
      (value "IPB80N04S2-H4")
      (footprint "IRF2804STRLPBF")
      (description "MOSFET (N-Channel)")
      (fields
        (field (name "MANUFACTURER_PART_NUMBER") "IRF1010NSPBF")
        (field (name "MOUSER PART NUMBER") "942-IRF1010NSPBF")
      )
      (libsource (lib "SamacSys") (part "IRF1010NSPBF"))
    )
    (comp (ref "Q14")
      (value "IPB80N04S2-H4")
      (footprint "IRF2804STRLPBF")
      (description "MOSFET (N-Channel)")
      (fields
        (field (name "MANUFACTURER_PART_NUMBER") "IRF1010NSPBF")
        (field (name "MOUSER PART NUMBER") "942-IRF1010NSPBF")
      )
      (libsource (lib "SamacSys") (part "IRF1010NSPBF"))
    )
    (comp (ref "Q15")
      (value "IPB80N04S2-H4")
      (footprint "IRF2804STRLPBF")
      (description "MOSFET (N-Channel)")
      (fields
        (field (name "MANUFACTURER_PART_NUMBER") "IRF1010NSPBF")
        (field (name "MOUSER PART NUMBER") "942-IRF1010NSPBF")
      )
      (libsource (lib "SamacSys") (part "IRF1010NSPBF"))
    )
    (comp (ref "Q16")
      (value "IPB80N04S2-H4")
      (footprint "IRF2804STRLPBF")
      (description "MOSFET (N-Channel)")
      (fields
        (field (name "MANUFACTURER_PART_NUMBER") "IRF1010NSPBF")
        (field (name "MOUSER PART NUMBER") "942-IRF1010NSPBF")
      )
      (libsource (lib "SamacSys") (part "IRF1010NSPBF"))
    )
    (comp (ref "Q17")
      (value "BC847B,215")
      (footprint "BC847B215")
      (description "Transistor BJT NPN")
      (fields (field (name "MOUSER PART NUMBER") "771-BC847B-T/R"))
      (libsource (lib "SamacSys") (part "BC847B,215"))
    )
    (comp (ref "Q18")
      (value "BC847B,215")
      (footprint "BC847B215")
      (description "Transistor BJT NPN")
      (fields (field (name "MOUSER PART NUMBER") "771-BC847B-T/R"))
      (libsource (lib "SamacSys") (part "BC847B,215"))
    )
    (comp (ref "Q19")
      (value "BC847B,215")
      (footprint "BC847B215")
      (description "Transistor BJT NPN")
      (fields (field (name "MOUSER PART NUMBER") "771-BC847B-T/R"))
      (libsource (lib "SamacSys") (part "BC847B,215"))
    )
    (comp (ref "Q20")
      (value "BC847B,215")
      (footprint "BC847B215")
      (description "Transistor BJT NPN")
      (fields (field (name "MOUSER PART NUMBER") "771-BC847B-T/R"))
      (libsource (lib "SamacSys") (part "BC847B,215"))
    )
    (comp (ref "Q21")
      (value "BC857,215")
      (footprint "BC857215")
      (description "Transistor BJT PNP")
      (fields (field (name "MOUSER PART NUMBER") "771-BC857215"))
      (libsource (lib "SamacSys") (part "BC857,215"))
    )
    (comp (ref "Q22")
      (value "BC857,215")
      (footprint "BC857215")
      (description "Transistor BJT PNP")
      (fields (field (name "MOUSER PART NUMBER") "771-BC857215"))
      (libsource (lib "SamacSys") (part "BC857,215"))
    )
    (comp (ref "Q23")
      (value "BC857,215")
      (footprint "BC857215")
      (description "Transistor BJT PNP")
      (fields (field (name "MOUSER PART NUMBER") "771-BC857215"))
      (libsource (lib "SamacSys") (part "BC857,215"))
    )
    (comp (ref "Q24")
      (value "BC857,215")
      (footprint "BC857215")
      (description "Transistor BJT PNP")
      (fields (field (name "MOUSER PART NUMBER") "771-BC857215"))
      (libsource (lib "SamacSys") (part "BC857,215"))
    )
    (comp (ref "Q25")
      (value "IPB80N04S2-H4")
      (footprint "IRF2804STRLPBF")
      (description "MOSFET (N-Channel)")
      (fields
        (field (name "MANUFACTURER_PART_NUMBER") "IRF1010NSPBF")
        (field (name "MOUSER PART NUMBER") "942-IRF1010NSPBF")
      )
      (libsource (lib "SamacSys") (part "IRF1010NSPBF"))
    )
    (comp (ref "Q26")
      (value "IPB80N04S2-H4")
      (footprint "IRF2804STRLPBF")
      (description "MOSFET (N-Channel)")
      (fields
        (field (name "MANUFACTURER_PART_NUMBER") "IRF1010NSPBF")
        (field (name "MOUSER PART NUMBER") "942-IRF1010NSPBF")
      )
      (libsource (lib "SamacSys") (part "IRF1010NSPBF"))
    )
    (comp (ref "Q27")
      (value "IPB80N04S2-H4")
      (footprint "IRF2804STRLPBF")
      (description "MOSFET (N-Channel)")
      (fields
        (field (name "MANUFACTURER_PART_NUMBER") "IRF1010NSPBF")
        (field (name "MOUSER PART NUMBER") "942-IRF1010NSPBF")
      )
      (libsource (lib "SamacSys") (part "IRF1010NSPBF"))
    )
    (comp (ref "Q28")
      (value "BC847B,215")
      (footprint "BC847B215")
      (description "Transistor BJT NPN")
      (fields (field (name "MOUSER PART NUMBER") "771-BC847B-T/R"))
      (libsource (lib "SamacSys") (part "BC847B,215"))
    )
    (comp (ref "Q29")
      (value "BC847B,215")
      (footprint "BC847B215")
      (description "Transistor BJT NPN")
      (fields (field (name "MOUSER PART NUMBER") "771-BC847B-T/R"))
      (libsource (lib "SamacSys") (part "BC847B,215"))
    )
    (comp (ref "Q30")
      (value "BC847B,215")
      (footprint "BC847B215")
      (description "Transistor BJT NPN")
      (fields (field (name "MOUSER PART NUMBER") "771-BC847B-T/R"))
      (libsource (lib "SamacSys") (part "BC847B,215"))
    )
    (comp (ref "Q31")
      (value "BC857,215")
      (footprint "BC857215")
      (description "Transistor BJT PNP")
      (fields (field (name "MOUSER PART NUMBER") "771-BC857215"))
      (libsource (lib "SamacSys") (part "BC857,215"))
    )
    (comp (ref "Q32")
      (value "BC857,215")
      (footprint "BC857215")
      (description "Transistor BJT PNP")
      (fields (field (name "MOUSER PART NUMBER") "771-BC857215"))
      (libsource (lib "SamacSys") (part "BC857,215"))
    )
    (comp (ref "Q33")
      (value "BC857,215")
      (footprint "BC857215")
      (description "Transistor BJT PNP")
      (fields (field (name "MOUSER PART NUMBER") "771-BC857215"))
      (libsource (lib "SamacSys") (part "BC857,215"))
    )
    (comp (ref "R1")
      (value "220")
      (footprint "0402 Resistor")
      (fields (field (name "Comment") "Resistor SMD"))
      (libsource (lib "ZetaBoard_Lib") (part "Resistor SMD"))
    )
    (comp (ref "R2")
      (value "10K")
      (footprint "0402 Resistor")
      (fields (field (name "Comment") "Resistor SMD"))
      (libsource (lib "ZetaBoard_Lib") (part "Resistor SMD"))
    )
    (comp (ref "R3")
      (value "10k")
      (footprint "0402 Resistor")
      (fields (field (name "Comment") "Resistor SMD"))
      (libsource (lib "ZetaBoard_Lib") (part "Resistor SMD"))
    )
    (comp (ref "R4")
      (value "10k")
      (footprint "0402 Resistor")
      (fields (field (name "Comment") "Resistor SMD"))
      (libsource (lib "ZetaBoard_Lib") (part "Resistor SMD"))
    )
    (comp (ref "R5")
      (value "10k")
      (footprint "0402 Resistor")
      (fields (field (name "Comment") "Resistor SMD"))
      (libsource (lib "ZetaBoard_Lib") (part "Resistor SMD"))
    )
    (comp (ref "R6")
      (value "10k")
      (footprint "0402 Resistor")
      (fields (field (name "Comment") "Resistor SMD"))
      (libsource (lib "ZetaBoard_Lib") (part "Resistor SMD"))
    )
    (comp (ref "R7")
      (value "0.01")
      (footprint "2512 Resistor")
      (fields (field (name "Comment") "Resistor SMD"))
      (libsource (lib "ZetaBoard_Lib") (part "Resistor SMD"))
    )
    (comp (ref "R8")
      (value "0.01")
      (footprint "2512 Resistor")
      (fields (field (name "Comment") "Resistor SMD"))
      (libsource (lib "ZetaBoard_Lib") (part "Resistor SMD"))
    )
    (comp (ref "R9")
      (value "0.01")
      (footprint "2512 Resistor")
      (fields (field (name "Comment") "Resistor SMD"))
      (libsource (lib "ZetaBoard_Lib") (part "Resistor SMD"))
    )
    (comp (ref "R10")
      (value "0")
      (footprint "0402 Resistor")
      (fields (field (name "Comment") "Resistor SMD"))
      (libsource (lib "ZetaBoard_Lib") (part "Resistor SMD"))
    )
    (comp (ref "R11")
      (value "4K")
      (footprint "0402 Resistor")
      (fields (field (name "Comment") "Resistor SMD"))
      (libsource (lib "ZetaBoard_Lib") (part "Resistor SMD"))
    )
    (comp (ref "R12")
      (value "0")
      (footprint "0402 Resistor")
      (fields (field (name "Comment") "Resistor SMD"))
      (libsource (lib "ZetaBoard_Lib") (part "Resistor SMD"))
    )
    (comp (ref "R13")
      (value "10K")
      (footprint "0402 Resistor")
      (fields (field (name "Comment") "Resistor SMD"))
      (libsource (lib "ZetaBoard_Lib") (part "Resistor SMD"))
    )
    (comp (ref "R14")
      (value "1.5K")
      (footprint "0402 Resistor")
      (fields (field (name "Comment") "Resistor SMD"))
      (libsource (lib "ZetaBoard_Lib") (part "Resistor SMD"))
    )
    (comp (ref "R15")
      (value "10")
      (footprint "0402 Resistor")
      (fields (field (name "Comment") "Resistor SMD"))
      (libsource (lib "ZetaBoard_Lib") (part "Resistor SMD"))
    )
    (comp (ref "R16")
      (value "22")
      (footprint "0402 Resistor")
      (fields (field (name "Comment") "Resistor SMD"))
      (libsource (lib "ZetaBoard_Lib") (part "Resistor SMD"))
    )
    (comp (ref "R17")
      (value "0")
      (footprint "0402 Resistor")
      (fields (field (name "Comment") "Resistor SMD"))
      (libsource (lib "ZetaBoard_Lib") (part "Resistor SMD"))
    )
    (comp (ref "R18")
      (value "22")
      (footprint "0402 Resistor")
      (fields (field (name "Comment") "Resistor SMD"))
      (libsource (lib "ZetaBoard_Lib") (part "Resistor SMD"))
    )
    (comp (ref "R19")
      (value "10")
      (footprint "0402 Resistor")
      (fields (field (name "Comment") "Resistor SMD"))
      (libsource (lib "ZetaBoard_Lib") (part "Resistor SMD"))
    )
    (comp (ref "R20")
      (value "10")
      (footprint "0402 Resistor")
      (fields (field (name "Comment") "Resistor SMD"))
      (libsource (lib "ZetaBoard_Lib") (part "Resistor SMD"))
    )
    (comp (ref "R21")
      (value "10")
      (footprint "0402 Resistor")
      (fields (field (name "Comment") "Resistor SMD"))
      (libsource (lib "ZetaBoard_Lib") (part "Resistor SMD"))
    )
    (comp (ref "R22")
      (value "2.2K")
      (footprint "0402 Resistor")
      (fields (field (name "Comment") "Resistor SMD"))
      (libsource (lib "ZetaBoard_Lib") (part "Resistor SMD"))
    )
    (comp (ref "R23")
      (value "2.2K")
      (footprint "0402 Resistor")
      (fields (field (name "Comment") "Resistor SMD"))
      (libsource (lib "ZetaBoard_Lib") (part "Resistor SMD"))
    )
    (comp (ref "R24")
      (value "2.2K")
      (footprint "0402 Resistor")
      (fields (field (name "Comment") "Resistor SMD"))
      (libsource (lib "ZetaBoard_Lib") (part "Resistor SMD"))
    )
    (comp (ref "R25")
      (value "2.2K")
      (footprint "0402 Resistor")
      (fields (field (name "Comment") "Resistor SMD"))
      (libsource (lib "ZetaBoard_Lib") (part "Resistor SMD"))
    )
    (comp (ref "R26")
      (value "1.3K")
      (footprint "0402 Resistor")
      (fields (field (name "Comment") "Resistor SMD"))
      (libsource (lib "ZetaBoard_Lib") (part "Resistor SMD"))
    )
    (comp (ref "R27")
      (value "1.3K")
      (footprint "0402 Resistor")
      (fields (field (name "Comment") "Resistor SMD"))
      (libsource (lib "ZetaBoard_Lib") (part "Resistor SMD"))
    )
    (comp (ref "R28")
      (value "1.3K")
      (footprint "0402 Resistor")
      (fields (field (name "Comment") "Resistor SMD"))
      (libsource (lib "ZetaBoard_Lib") (part "Resistor SMD"))
    )
    (comp (ref "R29")
      (value "10k")
      (footprint "0402 Resistor")
      (fields (field (name "Comment") "Resistor SMD"))
      (libsource (lib "ZetaBoard_Lib") (part "Resistor SMD"))
    )
    (comp (ref "R30")
      (value "1K")
      (footprint "0805 Resistor")
      (fields (field (name "Comment") "Resistor SMD"))
      (libsource (lib "ZetaBoard_Lib") (part "Resistor SMD"))
    )
    (comp (ref "R31")
      (value "10k")
      (footprint "0402 Resistor")
      (fields (field (name "Comment") "Resistor SMD"))
      (libsource (lib "ZetaBoard_Lib") (part "Resistor SMD"))
    )
    (comp (ref "R32")
      (value "10k")
      (footprint "0402 Resistor")
      (fields (field (name "Comment") "Resistor SMD"))
      (libsource (lib "ZetaBoard_Lib") (part "Resistor SMD"))
    )
    (comp (ref "R33")
      (value "1.3K")
      (footprint "0402 Resistor")
      (fields (field (name "Comment") "Resistor SMD"))
      (libsource (lib "ZetaBoard_Lib") (part "Resistor SMD"))
    )
    (comp (ref "R34")
      (value "10k")
      (footprint "0402 Resistor")
      (fields (field (name "Comment") "Resistor SMD"))
      (libsource (lib "ZetaBoard_Lib") (part "Resistor SMD"))
    )
    (comp (ref "R35")
      (value "0.01")
      (footprint "0805 Resistor")
      (fields (field (name "Comment") "Resistor SMD"))
      (libsource (lib "ZetaBoard_Lib") (part "Resistor SMD"))
    )
    (comp (ref "R36")
      (value "0.01")
      (footprint "2512 Resistor")
      (fields (field (name "Comment") "Resistor SMD"))
      (libsource (lib "ZetaBoard_Lib") (part "Resistor SMD"))
    )
    (comp (ref "R37")
      (value "0.01")
      (footprint "2512 Resistor")
      (fields (field (name "Comment") "Resistor SMD"))
      (libsource (lib "ZetaBoard_Lib") (part "Resistor SMD"))
    )
    (comp (ref "R38")
      (value "0.01")
      (footprint "2512 Resistor")
      (fields (field (name "Comment") "Resistor SMD"))
      (libsource (lib "ZetaBoard_Lib") (part "Resistor SMD"))
    )
    (comp (ref "R39")
      (value "10K")
      (footprint "0402 Resistor")
      (fields (field (name "Comment") "Resistor SMD"))
      (libsource (lib "ZetaBoard_Lib") (part "Resistor SMD"))
    )
    (comp (ref "R40")
      (value "10")
      (footprint "0402 Resistor")
      (fields (field (name "Comment") "Resistor SMD"))
      (libsource (lib "ZetaBoard_Lib") (part "Resistor SMD"))
    )
    (comp (ref "R41")
      (value "1K")
      (footprint "0402 Resistor")
      (fields (field (name "Comment") "Resistor SMD"))
      (libsource (lib "ZetaBoard_Lib") (part "Resistor SMD"))
    )
    (comp (ref "R42")
      (value "10")
      (footprint "0402 Resistor")
      (fields (field (name "Comment") "Resistor SMD"))
      (libsource (lib "ZetaBoard_Lib") (part "Resistor SMD"))
    )
    (comp (ref "R43")
      (value "10")
      (footprint "0402 Resistor")
      (fields (field (name "Comment") "Resistor SMD"))
      (libsource (lib "ZetaBoard_Lib") (part "Resistor SMD"))
    )
    (comp (ref "R44")
      (value "10")
      (footprint "0402 Resistor")
      (fields (field (name "Comment") "Resistor SMD"))
      (libsource (lib "ZetaBoard_Lib") (part "Resistor SMD"))
    )
    (comp (ref "R45")
      (value "2.2K")
      (footprint "0402 Resistor")
      (fields (field (name "Comment") "Resistor SMD"))
      (libsource (lib "ZetaBoard_Lib") (part "Resistor SMD"))
    )
    (comp (ref "R46")
      (value "2.2K")
      (footprint "0402 Resistor")
      (fields (field (name "Comment") "Resistor SMD"))
      (libsource (lib "ZetaBoard_Lib") (part "Resistor SMD"))
    )
    (comp (ref "R47")
      (value "2.2K")
      (footprint "0402 Resistor")
      (fields (field (name "Comment") "Resistor SMD"))
      (libsource (lib "ZetaBoard_Lib") (part "Resistor SMD"))
    )
    (comp (ref "R48")
      (value "2.2K")
      (footprint "0402 Resistor")
      (fields (field (name "Comment") "Resistor SMD"))
      (libsource (lib "ZetaBoard_Lib") (part "Resistor SMD"))
    )
    (comp (ref "R49")
      (value "10K")
      (footprint "0402 Resistor")
      (fields (field (name "Comment") "Resistor SMD"))
      (libsource (lib "ZetaBoard_Lib") (part "Resistor SMD"))
    )
    (comp (ref "R50")
      (value "10K")
      (footprint "0402 Resistor")
      (fields (field (name "Comment") "Resistor SMD"))
      (libsource (lib "ZetaBoard_Lib") (part "Resistor SMD"))
    )
    (comp (ref "R51")
      (value "31.6K")
      (footprint "0603 Resistor")
      (fields (field (name "Comment") "Resistor SMD"))
      (libsource (lib "ZetaBoard_Lib") (part "Resistor SMD"))
    )
    (comp (ref "R52")
      (value "100K")
      (footprint "0603 Resistor")
      (fields (field (name "Comment") "Resistor SMD"))
      (libsource (lib "ZetaBoard_Lib") (part "Resistor SMD"))
    )
    (comp (ref "R53")
      (value "10k")
      (footprint "0402 Resistor")
      (fields (field (name "Comment") "Resistor SMD"))
      (libsource (lib "ZetaBoard_Lib") (part "Resistor SMD"))
    )
    (comp (ref "R54")
      (value "10k")
      (footprint "0402 Resistor")
      (fields (field (name "Comment") "Resistor SMD"))
      (libsource (lib "ZetaBoard_Lib") (part "Resistor SMD"))
    )
    (comp (ref "R55")
      (value "10k")
      (footprint "0402 Resistor")
      (fields (field (name "Comment") "Resistor SMD"))
      (libsource (lib "ZetaBoard_Lib") (part "Resistor SMD"))
    )
    (comp (ref "R56")
      (value "0.01")
      (footprint "2512 Resistor")
      (fields (field (name "Comment") "Resistor SMD"))
      (libsource (lib "ZetaBoard_Lib") (part "Resistor SMD"))
    )
    (comp (ref "R57")
      (value "0.01")
      (footprint "2512 Resistor")
      (fields (field (name "Comment") "Resistor SMD"))
      (libsource (lib "ZetaBoard_Lib") (part "Resistor SMD"))
    )
    (comp (ref "R58")
      (value "1K")
      (footprint "0402 Resistor")
      (fields (field (name "Comment") "Resistor SMD"))
      (libsource (lib "ZetaBoard_Lib") (part "Resistor SMD"))
    )
    (comp (ref "R59")
      (value "10")
      (footprint "0402 Resistor")
      (fields (field (name "Comment") "Resistor SMD"))
      (libsource (lib "ZetaBoard_Lib") (part "Resistor SMD"))
    )
    (comp (ref "R60")
      (value "10")
      (footprint "0402 Resistor")
      (fields (field (name "Comment") "Resistor SMD"))
      (libsource (lib "ZetaBoard_Lib") (part "Resistor SMD"))
    )
    (comp (ref "R61")
      (value "10")
      (footprint "0402 Resistor")
      (fields (field (name "Comment") "Resistor SMD"))
      (libsource (lib "ZetaBoard_Lib") (part "Resistor SMD"))
    )
    (comp (ref "R62")
      (value "2.2K")
      (footprint "0402 Resistor")
      (fields (field (name "Comment") "Resistor SMD"))
      (libsource (lib "ZetaBoard_Lib") (part "Resistor SMD"))
    )
    (comp (ref "R63")
      (value "2.2K")
      (footprint "0402 Resistor")
      (fields (field (name "Comment") "Resistor SMD"))
      (libsource (lib "ZetaBoard_Lib") (part "Resistor SMD"))
    )
    (comp (ref "R64")
      (value "2.2K")
      (footprint "0402 Resistor")
      (fields (field (name "Comment") "Resistor SMD"))
      (libsource (lib "ZetaBoard_Lib") (part "Resistor SMD"))
    )
    (comp (ref "R65")
      (value "10K")
      (footprint "0402 Resistor")
      (fields (field (name "Comment") "Resistor SMD"))
      (libsource (lib "ZetaBoard_Lib") (part "Resistor SMD"))
    )
    (comp (ref "R66")
      (value "10K")
      (footprint "0402 Resistor")
      (fields (field (name "Comment") "Resistor SMD"))
      (libsource (lib "ZetaBoard_Lib") (part "Resistor SMD"))
    )
    (comp (ref "R67")
      (value "2K")
      (footprint "0402 Resistor")
      (fields (field (name "Comment") "Resistor SMD"))
      (libsource (lib "ZetaBoard_Lib") (part "Resistor SMD"))
    )
    (comp (ref "R68")
      (value "15.K")
      (footprint "0402 Resistor")
      (fields (field (name "Comment") "Resistor SMD"))
      (libsource (lib "ZetaBoard_Lib") (part "Resistor SMD"))
    )
    (comp (ref "R69")
      (value "4.7K")
      (footprint "0402 Resistor")
      (fields (field (name "ALTIUM_UNNAMED_1") "4.7K"))
      (libsource (lib "ZetaBoard_Lib") (part "Resistor SMD"))
    )
    (comp (ref "R70")
      (value "15.K")
      (footprint "0402 Resistor")
      (fields (field (name "Comment") "Resistor SMD"))
      (libsource (lib "ZetaBoard_Lib") (part "Resistor SMD"))
    )
    (comp (ref "R71")
      (value "4.7K")
      (footprint "0402 Resistor")
      (fields (field (name "ALTIUM_UNNAMED_1") "4.7K"))
      (libsource (lib "ZetaBoard_Lib") (part "Resistor SMD"))
    )
    (comp (ref "R72")
      (value "4.7K")
      (footprint "0402 Resistor")
      (fields (field (name "ALTIUM_UNNAMED_1") "4.7K"))
      (libsource (lib "ZetaBoard_Lib") (part "Resistor SMD"))
    )
    (comp (ref "R73")
      (value "4.7K")
      (footprint "0402 Resistor")
      (fields (field (name "ALTIUM_UNNAMED_1") "4.7K"))
      (libsource (lib "ZetaBoard_Lib") (part "Resistor SMD"))
    )
    (comp (ref "R74")
      (value "4.7K")
      (footprint "0402 Resistor")
      (fields (field (name "ALTIUM_UNNAMED_1") "4.7K"))
      (libsource (lib "ZetaBoard_Lib") (part "Resistor SMD"))
    )
    (comp (ref "R75")
      (value "4.7K")
      (footprint "0402 Resistor")
      (fields (field (name "ALTIUM_UNNAMED_1") "4.7K"))
      (libsource (lib "ZetaBoard_Lib") (part "Resistor SMD"))
    )
    (comp (ref "R76")
      (value "4.7K")
      (footprint "0402 Resistor")
      (fields (field (name "ALTIUM_UNNAMED_1") "4.7K"))
      (libsource (lib "ZetaBoard_Lib") (part "Resistor SMD"))
    )
    (comp (ref "R77")
      (value "4.7K")
      (footprint "0402 Resistor")
      (fields (field (name "ALTIUM_UNNAMED_1") "4.7K"))
      (libsource (lib "ZetaBoard_Lib") (part "Resistor SMD"))
    )
    (comp (ref "R78")
      (value "4.7K")
      (footprint "0402 Resistor")
      (fields (field (name "ALTIUM_UNNAMED_1") "4.7K"))
      (libsource (lib "ZetaBoard_Lib") (part "Resistor SMD"))
    )
    (comp (ref "R79")
      (value "4.7K")
      (footprint "0402 Resistor")
      (fields (field (name "ALTIUM_UNNAMED_1") "4.7K"))
      (libsource (lib "ZetaBoard_Lib") (part "Resistor SMD"))
    )
    (comp (ref "R80")
      (value "4.7K")
      (footprint "0402 Resistor")
      (fields (field (name "ALTIUM_UNNAMED_1") "4.7K"))
      (libsource (lib "ZetaBoard_Lib") (part "Resistor SMD"))
    )
    (comp (ref "R81")
      (value "4.7K")
      (footprint "0402 Resistor")
      (fields (field (name "ALTIUM_UNNAMED_1") "4.7K"))
      (libsource (lib "ZetaBoard_Lib") (part "Resistor SMD"))
    )
    (comp (ref "R82")
      (value "0")
      (footprint "0603 Resistor")
      (fields (field (name "ALTIUM_UNNAMED_1") "0"))
      (libsource (lib "ZetaBoard_Lib") (part "Resistor SMD"))
    )
    (comp (ref "R83")
      (value "4.7K")
      (footprint "0402 Resistor")
      (fields (field (name "ALTIUM_UNNAMED_1") "4.7K"))
      (libsource (lib "ZetaBoard_Lib") (part "Resistor SMD"))
    )
    (comp (ref "R84")
      (value "4.7K")
      (footprint "0402 Resistor")
      (fields (field (name "ALTIUM_UNNAMED_1") "4.7K"))
      (libsource (lib "ZetaBoard_Lib") (part "Resistor SMD"))
    )
    (comp (ref "R85")
      (value "4.7K")
      (footprint "0402 Resistor")
      (fields (field (name "ALTIUM_UNNAMED_1") "4.7K"))
      (libsource (lib "ZetaBoard_Lib") (part "Resistor SMD"))
    )
    (comp (ref "R86")
      (value "4.7K")
      (footprint "0402 Resistor")
      (fields (field (name "ALTIUM_UNNAMED_1") "4.7K"))
      (libsource (lib "ZetaBoard_Lib") (part "Resistor SMD"))
    )
    (comp (ref "R87")
      (value "4.7K")
      (footprint "0402 Resistor")
      (fields (field (name "ALTIUM_UNNAMED_1") "4.7K"))
      (libsource (lib "ZetaBoard_Lib") (part "Resistor SMD"))
    )
    (comp (ref "R88")
      (value "4.7K")
      (footprint "0402 Resistor")
      (fields (field (name "ALTIUM_UNNAMED_1") "4.7K"))
      (libsource (lib "ZetaBoard_Lib") (part "Resistor SMD"))
    )
    (comp (ref "R89")
      (value "70K")
      (footprint "0402 Resistor")
      (fields (field (name "Comment") "Resistor SMD"))
      (libsource (lib "ZetaBoard_Lib") (part "Resistor SMD"))
    )
    (comp (ref "S1")
      (value "1571983-1")
      (footprint "SamacSys:15719831")
      (description "Switch")
      (libsource (lib "SamacSys") (part "1571983-1"))
    )
    (comp (ref "Y1")
      (value "16Mhz")
      (footprint "Xtal 2p SMD")
      (libsource (lib "ZetaBoard_Lib") (part "Xtal"))
    )
    (comp (ref "Z1")
      (value "1SMA4753A")
      (footprint "DIOM5527X250N")
      (description "Zener Diode")
      (libsource (lib "SamacSys") (part "1SMA4753A"))
    )
    (comp (ref "Z2")
      (value "1SMA4753A")
      (footprint "DIOM5527X250N")
      (description "Zener Diode")
      (libsource (lib "SamacSys") (part "1SMA4753A"))
    )
    (comp (ref "Z3")
      (value "1SMA4753A")
      (footprint "DIOM5527X250N")
      (description "Zener Diode")
      (libsource (lib "SamacSys") (part "1SMA4753A"))
    )
    (comp (ref "Z4")
      (value "1SMA4753A")
      (footprint "DIOM5527X250N")
      (description "Zener Diode")
      (libsource (lib "SamacSys") (part "1SMA4753A"))
    )
    (comp (ref "Z5")
      (value "~")
      (footprint "BZV55C3V3L1")
      (description "Zener Diode 30V")
      (fields
        (field (name "MANUFACTURER_PART_NUMBER") "BZV55C3V3 L1")
        (field (name "MOUSER PART NUMBER") "821-BZV55C3V3L1")
      )
      (libsource (lib "SamacSys") (part "BZV55C3V3_L1"))
    )
    (comp (ref "Z6")
      (value "1SMA4753A")
      (footprint "DIOM5527X250N")
      (description "Zener Diode")
      (libsource (lib "SamacSys") (part "1SMA4753A"))
    )
    (comp (ref "Z7")
      (value "1SMA4753A")
      (footprint "DIOM5527X250N")
      (description "Zener Diode")
      (libsource (lib "SamacSys") (part "1SMA4753A"))
    )
    (comp (ref "Z8")
      (value "1SMA4753A")
      (footprint "DIOM5527X250N")
      (description "Zener Diode")
      (libsource (lib "SamacSys") (part "1SMA4753A"))
    )
    (comp (ref "Z9")
      (value "1SMA4753A")
      (footprint "DIOM5527X250N")
      (description "Zener Diode")
      (libsource (lib "SamacSys") (part "1SMA4753A"))
    )
    (comp (ref "Z10")
      (value "~")
      (footprint "BZV55C3V3L1")
      (description "Zener Diode 3.3V")
      (fields
        (field (name "MANUFACTURER_PART_NUMBER") "BZV55C3V3 L1")
        (field (name "MOUSER PART NUMBER") "821-BZV55C3V3L1")
      )
      (libsource (lib "SamacSys") (part "BZV55C3V3_L1"))
    )
    (comp (ref "Z11")
      (value "~")
      (footprint "BZV55C3V3L1")
      (description "Zener Diode 5V")
      (fields
        (field (name "MANUFACTURER_PART_NUMBER") "BZV55C3V3 L1")
        (field (name "MOUSER PART NUMBER") "821-BZV55C3V3L1")
      )
      (libsource (lib "SamacSys") (part "BZV55C3V3_L1"))
    )
    (comp (ref "Z12")
      (value "1SMA4753A")
      (footprint "DIOM5527X250N")
      (description "Zener Diode")
      (libsource (lib "SamacSys") (part "1SMA4753A"))
    )
    (comp (ref "Z13")
      (value "1SMA4753A")
      (footprint "DIOM5527X250N")
      (description "Zener Diode")
      (libsource (lib "SamacSys") (part "1SMA4753A"))
    )
    (comp (ref "Z14")
      (value "1SMA4753A")
      (footprint "DIOM5527X250N")
      (description "Zener Diode")
      (libsource (lib "SamacSys") (part "1SMA4753A"))
    )
    (comp (ref "Z15")
      (value "BZV55C3V3_L1")
      (footprint "BZV55C3V3L1")
      (description "Zener Diode 3.3V")
      (fields
        (field (name "MANUFACTURER_PART_NUMBER") "BZV55C3V3 L1")
        (field (name "MOUSER PART NUMBER") "821-BZV55C3V3L1")
      )
      (libsource (lib "SamacSys") (part "BZV55C3V3_L1"))
    )
    (comp (ref "Z16")
      (value "BZV55C3V3_L1")
      (footprint "SamacSys:BZV55C3V3L1")
      (description "Zener Diode 3.3v")
      (fields
        (field (name "MANUFACTURER_PART_NUMBER") "BZV55C3V3 L1")
        (field (name "MOUSER PART NUMBER") "821-BZV55C3V3L1")
      )
      (libsource (lib "SamacSys") (part "BZV55C3V3_L1"))
    )
    (comp (ref "Z17")
      (value "BZV55C3V3_L1")
      (footprint "BZV55C3V3L1")
      (description "Zener Diode 3.3V")
      (fields
        (field (name "MANUFACTURER_PART_NUMBER") "BZV55C3V3 L1")
        (field (name "MOUSER PART NUMBER") "821-BZV55C3V3L1")
      )
      (libsource (lib "SamacSys") (part "BZV55C3V3_L1"))
    )
    (comp (ref "Z18")
      (value "BZV55C3V3_L1")
      (footprint "BZV55C3V3L1")
      (description "Zener Diode 3.3V")
      (fields
        (field (name "MANUFACTURER_PART_NUMBER") "BZV55C3V3 L1")
        (field (name "MOUSER PART NUMBER") "821-BZV55C3V3L1")
      )
      (libsource (lib "SamacSys") (part "BZV55C3V3_L1"))
    )
  )
  (nets
    (net (code "1") (name "+5") (class "Default")
      (node (ref "C26") (pin "1") (pintype "passive"))
      (node (ref "C27") (pin "2") (pintype "passive"))
      (node (ref "C37") (pin "1") (pintype "passive"))
      (node (ref "C38") (pin "2") (pintype "passive"))
      (node (ref "C54") (pin "2") (pintype "passive"))
      (node (ref "C55") (pin "1") (pinfunction "+_1") (pintype "passive"))
      (node (ref "C63") (pin "1") (pintype "passive"))
      (node (ref "CN1") (pin "12") (pinfunction "12_12") (pintype "passive"))
      (node (ref "CN1") (pin "24") (pinfunction "24_24") (pintype "passive"))
      (node (ref "D1") (pin "2") (pintype "passive"))
      (node (ref "D13") (pin "2") (pintype "passive"))
      (node (ref "D14") (pin "2") (pintype "passive"))
      (node (ref "IC12") (pin "4") (pinfunction "OUT_4") (pintype "passive"))
      (node (ref "IC15") (pin "3") (pinfunction "VIN_3") (pintype "passive"))
      (node (ref "IC6") (pin "3") (pinfunction "VCC_3") (pintype "passive"))
      (node (ref "IC7") (pin "3") (pinfunction "VCC_3") (pintype "passive"))
      (node (ref "R52") (pin "2") (pintype "passive"))
      (node (ref "R67") (pin "1") (pintype "passive"))
      (node (ref "Z11") (pin "1") (pinfunction "K_1") (pintype "passive"))
    )
    (net (code "2") (name "/BOOT0") (class "Default")
      (node (ref "IC1") (pin "60") (pinfunction "BOOT0_60") (pintype "passive"))
      (node (ref "R49") (pin "1") (pintype "passive"))
      (node (ref "S1") (pin "1") (pinfunction "1_1") (pintype "passive"))
    )
    (net (code "3") (name "/BOOT1") (class "Default")
      (node (ref "IC1") (pin "28") (pinfunction "PB2_28") (pintype "passive"))
      (node (ref "R50") (pin "2") (pintype "passive"))
      (node (ref "S1") (pin "3") (pinfunction "3_3") (pintype "passive"))
    )
    (net (code "4") (name "/BRAKE_SIG") (class "Default")
      (node (ref "CN1") (pin "5") (pinfunction "5_5") (pintype "passive"))
      (node (ref "R80") (pin "1") (pintype "passive"))
    )
    (net (code "5") (name "/BRAKE_SNS") (class "Default")
      (node (ref "IC1") (pin "3") (pinfunction "PC14-OSC32_IN_3") (pintype "input"))
      (node (ref "IC17") (pin "16") (pinfunction "COLLECTOR_4_16") (pintype "passive"))
      (node (ref "R72") (pin "2") (pintype "passive"))
    )
    (net (code "6") (name "/CAN1") (class "Default")
      (node (ref "IC1") (pin "59") (pinfunction "PB7_59") (pintype "passive"))
      (node (ref "IC6") (pin "8") (pinfunction "S_8") (pintype "passive"))
    )
    (net (code "7") (name "/CAN2") (class "Default")
      (node (ref "IC1") (pin "56") (pinfunction "PB4_56") (pintype "passive"))
      (node (ref "IC7") (pin "8") (pinfunction "S_8") (pintype "passive"))
    )
    (net (code "8") (name "/Current_sens") (class "Default")
      (node (ref "IC1") (pin "14") (pinfunction "PA0-WKUP_14") (pintype "passive"))
      (node (ref "IC8") (pin "1") (pinfunction "OUT_1") (pintype "passive"))
    )
    (net (code "9") (name "/D+") (class "Default")
      (node (ref "IC1") (pin "45") (pinfunction "PA12_45") (pintype "passive"))
      (node (ref "R18") (pin "1") (pintype "passive"))
    )
    (net (code "10") (name "/D-") (class "Default")
      (node (ref "IC1") (pin "44") (pinfunction "PA11_44") (pintype "passive"))
      (node (ref "R16") (pin "1") (pintype "passive"))
    )
    (net (code "11") (name "/E2P_EN") (class "Default")
      (node (ref "IC5") (pin "7") (pinfunction "~{WC}_7") (pintype "passive"))
      (node (ref "R10") (pin "2") (pintype "passive"))
      (node (ref "R13") (pin "2") (pintype "passive"))
      (node (ref "R17") (pin "1") (pintype "passive"))
    )
    (net (code "12") (name "/E2P_SCL") (class "Default")
      (node (ref "IC1") (pin "29") (pinfunction "PB10_29") (pintype "passive"))
      (node (ref "IC5") (pin "6") (pinfunction "SCL_6") (pintype "passive"))
    )
    (net (code "13") (name "/E2P_SDA") (class "Default")
      (node (ref "C15") (pin "1") (pintype "passive"))
      (node (ref "IC1") (pin "30") (pinfunction "PB11_30") (pintype "passive"))
      (node (ref "IC5") (pin "5") (pinfunction "SDA_5") (pintype "passive"))
      (node (ref "R11") (pin "2") (pintype "passive"))
    )
    (net (code "14") (name "/H1") (class "Default")
      (node (ref "CN1") (pin "16") (pinfunction "16_16") (pintype "passive"))
      (node (ref "IC6") (pin "7") (pinfunction "CANH_7") (pintype "passive"))
      (node (ref "R26") (pin "2") (pintype "passive"))
    )
    (net (code "15") (name "/H2") (class "Default")
      (node (ref "CN1") (pin "15") (pinfunction "15_15") (pintype "passive"))
      (node (ref "IC7") (pin "7") (pinfunction "CANH_7") (pintype "passive"))
      (node (ref "R28") (pin "2") (pintype "passive"))
    )
    (net (code "16") (name "/IGNITION") (class "Default")
      (node (ref "CN1") (pin "17") (pinfunction "17_17") (pintype "passive"))
      (node (ref "R83") (pin "1") (pintype "passive"))
    )
    (net (code "17") (name "/IGNITION_SNS") (class "Default")
      (node (ref "IC1") (pin "4") (pinfunction "PC15-OSC32_OUT_4") (pintype "output"))
      (node (ref "IC17") (pin "14") (pinfunction "COLLECTOR_3_14") (pintype "passive"))
      (node (ref "R73") (pin "2") (pintype "passive"))
    )
    (net (code "18") (name "/L1") (class "Default")
      (node (ref "CN1") (pin "4") (pinfunction "4_4") (pintype "passive"))
      (node (ref "IC6") (pin "6") (pinfunction "CANL_6") (pintype "passive"))
      (node (ref "R27") (pin "1") (pintype "passive"))
    )
    (net (code "19") (name "/L2") (class "Default")
      (node (ref "CN1") (pin "3") (pinfunction "3_3") (pintype "passive"))
      (node (ref "IC7") (pin "6") (pinfunction "CANL_6") (pintype "passive"))
      (node (ref "R33") (pin "1") (pintype "passive"))
    )
    (net (code "20") (name "/LPS") (class "Default")
      (node (ref "CN1") (pin "22") (pinfunction "22_22") (pintype "passive"))
      (node (ref "R65") (pin "1") (pintype "passive"))
    )
    (net (code "21") (name "/LPS_SNS") (class "Default")
      (node (ref "IC1") (pin "10") (pinfunction "PC2_10") (pintype "passive"))
      (node (ref "R65") (pin "2") (pintype "passive"))
      (node (ref "R68") (pin "1") (pintype "passive"))
      (node (ref "Z16") (pin "1") (pinfunction "K_1") (pintype "passive"))
    )
    (net (code "22") (name "/MOD_1") (class "Default")
      (node (ref "IC1") (pin "33") (pinfunction "PB12_33") (pintype "passive"))
      (node (ref "IC17") (pin "12") (pinfunction "COLLECTOR_2_12") (pintype "passive"))
      (node (ref "R74") (pin "2") (pintype "passive"))
    )
    (net (code "23") (name "/MOD_2") (class "Default")
      (node (ref "IC1") (pin "34") (pinfunction "PB13_34") (pintype "passive"))
      (node (ref "IC17") (pin "10") (pinfunction "COLLECTOR_1_10") (pintype "passive"))
      (node (ref "R75") (pin "2") (pintype "passive"))
    )
    (net (code "24") (name "/MOD_IN_1") (class "Default")
      (node (ref "CN1") (pin "6") (pinfunction "6_6") (pintype "passive"))
      (node (ref "R85") (pin "1") (pintype "passive"))
    )
    (net (code "25") (name "/MOD_IN_2") (class "Default")
      (node (ref "CN1") (pin "18") (pinfunction "18_18") (pintype "passive"))
      (node (ref "R87") (pin "1") (pintype "passive"))
    )
    (net (code "26") (name "/MOS_IN_1") (class "Default")
      (node (ref "C5") (pin "2") (pintype "passive"))
      (node (ref "CN2") (pin "14") (pinfunction "14_14") (pintype "passive"))
      (node (ref "IC2") (pin "3") (pinfunction "IN+_3") (pintype "passive"))
      (node (ref "LD2") (pin "2") (pinfunction "K_2") (pintype "passive"))
      (node (ref "R7") (pin "2") (pintype "passive"))
      (node (ref "Z1") (pin "2") (pinfunction "A_2") (pintype "passive"))
    )
    (net (code "27") (name "/MOS_IN_2") (class "Default")
      (node (ref "C6") (pin "2") (pintype "passive"))
      (node (ref "CN2") (pin "16") (pinfunction "16_16") (pintype "passive"))
      (node (ref "IC3") (pin "3") (pinfunction "IN+_3") (pintype "passive"))
      (node (ref "LD3") (pin "2") (pinfunction "K_2") (pintype "passive"))
      (node (ref "R8") (pin "2") (pintype "passive"))
      (node (ref "Z2") (pin "2") (pinfunction "A_2") (pintype "passive"))
    )
    (net (code "28") (name "/MOS_IN_3") (class "Default")
      (node (ref "C7") (pin "2") (pintype "passive"))
      (node (ref "CN2") (pin "19") (pinfunction "19_19") (pintype "passive"))
      (node (ref "IC4") (pin "3") (pinfunction "IN+_3") (pintype "passive"))
      (node (ref "LD4") (pin "2") (pinfunction "K_2") (pintype "passive"))
      (node (ref "R9") (pin "2") (pintype "passive"))
      (node (ref "Z3") (pin "2") (pinfunction "A_2") (pintype "passive"))
    )
    (net (code "29") (name "/MOS_IN_4") (class "Default")
      (node (ref "C34") (pin "2") (pintype "passive"))
      (node (ref "CN2") (pin "22") (pinfunction "22_22") (pintype "passive"))
      (node (ref "IC10") (pin "3") (pinfunction "IN+_3") (pintype "passive"))
      (node (ref "LD7") (pin "2") (pinfunction "K_2") (pintype "passive"))
      (node (ref "R37") (pin "2") (pintype "passive"))
      (node (ref "Z7") (pin "2") (pinfunction "A_2") (pintype "passive"))
    )
    (net (code "30") (name "/MOS_IN_5") (class "Default")
      (node (ref "C35") (pin "2") (pintype "passive"))
      (node (ref "CN2") (pin "15") (pinfunction "15_15") (pintype "passive"))
      (node (ref "IC11") (pin "3") (pinfunction "IN+_3") (pintype "passive"))
      (node (ref "LD8") (pin "2") (pinfunction "K_2") (pintype "passive"))
      (node (ref "R38") (pin "2") (pintype "passive"))
      (node (ref "Z8") (pin "2") (pinfunction "A_2") (pintype "passive"))
    )
    (net (code "31") (name "/MOS_IN_6") (class "Default")
      (node (ref "C33") (pin "2") (pintype "passive"))
      (node (ref "CN2") (pin "17") (pinfunction "17_17") (pintype "passive"))
      (node (ref "IC9") (pin "3") (pinfunction "IN+_3") (pintype "passive"))
      (node (ref "LD6") (pin "2") (pinfunction "K_2") (pintype "passive"))
      (node (ref "R36") (pin "2") (pintype "passive"))
      (node (ref "Z6") (pin "2") (pinfunction "A_2") (pintype "passive"))
    )
    (net (code "32") (name "/MOS_IN_7") (class "Default")
      (node (ref "C57") (pin "2") (pintype "passive"))
      (node (ref "CN2") (pin "20") (pinfunction "20_20") (pintype "passive"))
      (node (ref "IC14") (pin "3") (pinfunction "IN+_3") (pintype "passive"))
      (node (ref "LD11") (pin "2") (pinfunction "K_2") (pintype "passive"))
      (node (ref "R57") (pin "2") (pintype "passive"))
      (node (ref "Z13") (pin "2") (pinfunction "A_2") (pintype "passive"))
    )
    (net (code "33") (name "/MOS_IN_8") (class "Default")
      (node (ref "C56") (pin "2") (pintype "passive"))
      (node (ref "CN2") (pin "23") (pinfunction "23_23") (pintype "passive"))
      (node (ref "IC13") (pin "3") (pinfunction "IN+_3") (pintype "passive"))
      (node (ref "LD10") (pin "2") (pinfunction "K_2") (pintype "passive"))
      (node (ref "R56") (pin "2") (pintype "passive"))
      (node (ref "Z12") (pin "2") (pinfunction "A_2") (pintype "passive"))
    )
    (net (code "34") (name "/MOS_IN_9") (class "Default")
      (node (ref "C58") (pin "2") (pintype "passive"))
      (node (ref "CN2") (pin "24") (pinfunction "24_24") (pintype "passive"))
      (node (ref "LD12") (pin "2") (pinfunction "K_2") (pintype "passive"))
      (node (ref "Q25") (pin "2") (pinfunction "D_2") (pintype "passive"))
      (node (ref "Z14") (pin "2") (pinfunction "A_2") (pintype "passive"))
    )
    (net (code "35") (name "/MOS_IN_10") (class "Default")
      (node (ref "C10") (pin "2") (pintype "passive"))
      (node (ref "CN2") (pin "21") (pinfunction "21_21") (pintype "passive"))
      (node (ref "LD5") (pin "2") (pinfunction "K_2") (pintype "passive"))
      (node (ref "Q1") (pin "2") (pinfunction "D_2") (pintype "passive"))
      (node (ref "Z4") (pin "2") (pinfunction "A_2") (pintype "passive"))
    )
    (net (code "36") (name "/MOS_IN_11") (class "Default")
      (node (ref "C36") (pin "2") (pintype "passive"))
      (node (ref "CN2") (pin "18") (pinfunction "18_18") (pintype "passive"))
      (node (ref "LD9") (pin "2") (pinfunction "K_2") (pintype "passive"))
      (node (ref "Q13") (pin "2") (pinfunction "D_2") (pintype "passive"))
      (node (ref "Z9") (pin "2") (pinfunction "A_2") (pintype "passive"))
    )
    (net (code "37") (name "/MOS_PWM_1") (class "Default")
      (node (ref "IC1") (pin "16") (pinfunction "PA2_16") (pintype "passive"))
      (node (ref "R23") (pin "2") (pintype "passive"))
    )
    (net (code "38") (name "/MOS_PWM_2") (class "Default")
      (node (ref "IC1") (pin "17") (pinfunction "PA3_17") (pintype "passive"))
      (node (ref "R24") (pin "2") (pintype "passive"))
    )
    (net (code "39") (name "/MOS_PWM_3") (class "Default")
      (node (ref "IC1") (pin "35") (pinfunction "PB14_35") (pintype "passive"))
      (node (ref "R25") (pin "2") (pintype "passive"))
    )
    (net (code "40") (name "/MOS_PWM_4") (class "Default")
      (node (ref "IC1") (pin "36") (pinfunction "PB15_36") (pintype "passive"))
      (node (ref "R47") (pin "2") (pintype "passive"))
    )
    (net (code "41") (name "/MOS_PWM_5") (class "Default")
      (node (ref "IC1") (pin "37") (pinfunction "PC6_37") (pintype "passive"))
      (node (ref "R48") (pin "2") (pintype "passive"))
    )
    (net (code "42") (name "/MOS_PWM_6") (class "Default")
      (node (ref "IC1") (pin "38") (pinfunction "PC7_38") (pintype "passive"))
      (node (ref "R46") (pin "2") (pintype "passive"))
    )
    (net (code "43") (name "/MOS_PWM_7") (class "Default")
      (node (ref "IC1") (pin "39") (pinfunction "PC8_39") (pintype "passive"))
      (node (ref "R64") (pin "2") (pintype "passive"))
    )
    (net (code "44") (name "/MOS_PWM_8") (class "Default")
      (node (ref "IC1") (pin "40") (pinfunction "PC9_40") (pintype "passive"))
      (node (ref "R63") (pin "2") (pintype "passive"))
    )
    (net (code "45") (name "/MOS_PWM_9") (class "Default")
      (node (ref "IC1") (pin "55") (pinfunction "PB3_55") (pintype "passive"))
      (node (ref "R62") (pin "2") (pintype "passive"))
    )
    (net (code "46") (name "/MOS_PWM_10") (class "Default")
      (node (ref "IC1") (pin "50") (pinfunction "PA15_50") (pintype "passive"))
      (node (ref "R22") (pin "2") (pintype "passive"))
    )
    (net (code "47") (name "/MOS_PWM_11") (class "Default")
      (node (ref "R12") (pin "1") (pintype "passive"))
      (node (ref "R45") (pin "2") (pintype "passive"))
    )
    (net (code "48") (name "/MOS_SENSE_1") (class "Default")
      (node (ref "IC1") (pin "20") (pinfunction "PA4_20") (pintype "passive"))
      (node (ref "IC2") (pin "1") (pinfunction "OUT_1") (pintype "passive"))
    )
    (net (code "49") (name "/MOS_SENSE_2") (class "Default")
      (node (ref "IC1") (pin "21") (pinfunction "PA5_21") (pintype "passive"))
      (node (ref "IC3") (pin "1") (pinfunction "OUT_1") (pintype "passive"))
    )
    (net (code "50") (name "/MOS_SENSE_3") (class "Default")
      (node (ref "IC1") (pin "22") (pinfunction "PA6_22") (pintype "passive"))
      (node (ref "IC4") (pin "1") (pinfunction "OUT_1") (pintype "passive"))
    )
    (net (code "51") (name "/MOS_SENSE_4") (class "Default")
      (node (ref "IC1") (pin "23") (pinfunction "PA7_23") (pintype "passive"))
      (node (ref "IC10") (pin "1") (pinfunction "OUT_1") (pintype "passive"))
    )
    (net (code "52") (name "/MOS_SENSE_5") (class "Default")
      (node (ref "IC1") (pin "24") (pinfunction "PC4_24") (pintype "passive"))
      (node (ref "IC11") (pin "1") (pinfunction "OUT_1") (pintype "passive"))
    )
    (net (code "53") (name "/MOS_SENSE_6") (class "Default")
      (node (ref "IC1") (pin "25") (pinfunction "PC5_25") (pintype "passive"))
      (node (ref "IC9") (pin "1") (pinfunction "OUT_1") (pintype "passive"))
    )
    (net (code "54") (name "/MOS_SENSE_7") (class "Default")
      (node (ref "IC1") (pin "26") (pinfunction "PB0_26") (pintype "passive"))
      (node (ref "IC14") (pin "1") (pinfunction "OUT_1") (pintype "passive"))
      (node (ref "P3") (pin "1") (pinfunction "1_1") (pintype "passive"))
    )
    (net (code "55") (name "/MOS_SENSE_8") (class "Default")
      (node (ref "IC1") (pin "27") (pinfunction "PB1_27") (pintype "passive"))
      (node (ref "IC13") (pin "1") (pinfunction "OUT_1") (pintype "passive"))
      (node (ref "P3") (pin "2") (pinfunction "2_2") (pintype "passive"))
    )
    (net (code "56") (name "/RXD1") (class "Default")
      (node (ref "IC1") (pin "61") (pinfunction "PB8_61") (pintype "passive"))
      (node (ref "IC6") (pin "4") (pinfunction "RXD_4") (pintype "passive"))
    )
    (net (code "57") (name "/RXD2") (class "Default")
      (node (ref "IC1") (pin "57") (pinfunction "PB5_57") (pintype "passive"))
      (node (ref "IC7") (pin "4") (pinfunction "RXD_4") (pintype "passive"))
    )
    (net (code "58") (name "/SELECTOR_1") (class "Default")
      (node (ref "IC1") (pin "51") (pinfunction "PC10_51") (pintype "passive"))
      (node (ref "IC18") (pin "16") (pinfunction "COLLECTOR_4_16") (pintype "passive"))
      (node (ref "R76") (pin "2") (pintype "passive"))
    )
    (net (code "59") (name "/SELECTOR_2") (class "Default")
      (node (ref "IC1") (pin "52") (pinfunction "PC11_52") (pintype "passive"))
      (node (ref "IC18") (pin "14") (pinfunction "COLLECTOR_3_14") (pintype "passive"))
      (node (ref "R77") (pin "2") (pintype "passive"))
    )
    (net (code "60") (name "/SELECTOR_IN_1") (class "Default")
      (node (ref "CN1") (pin "1") (pinfunction "1_1") (pintype "passive"))
      (node (ref "R81") (pin "1") (pintype "passive"))
    )
    (net (code "61") (name "/SELECTOR_IN_2") (class "Default")
      (node (ref "CN1") (pin "13") (pinfunction "13_13") (pintype "passive"))
      (node (ref "R84") (pin "1") (pintype "passive"))
    )
    (net (code "62") (name "/SER_RX") (class "Default")
      (node (ref "IC1") (pin "43") (pinfunction "PA10_43") (pintype "passive"))
      (node (ref "P1") (pin "2") (pinfunction "2_2") (pintype "passive"))
    )
    (net (code "63") (name "/SER_TX") (class "Default")
      (node (ref "IC1") (pin "42") (pinfunction "PA9_42") (pintype "passive"))
      (node (ref "P1") (pin "3") (pinfunction "3_3") (pintype "passive"))
    )
    (net (code "64") (name "/SHIFT_DOWN") (class "Default")
      (node (ref "IC1") (pin "54") (pinfunction "PD2_54") (pintype "passive"))
      (node (ref "IC18") (pin "10") (pinfunction "COLLECTOR_1_10") (pintype "passive"))
      (node (ref "R79") (pin "2") (pintype "passive"))
    )
    (net (code "65") (name "/SHIFT_DOWN_IN") (class "Default")
      (node (ref "CN1") (pin "14") (pinfunction "14_14") (pintype "passive"))
      (node (ref "R88") (pin "1") (pintype "passive"))
    )
    (net (code "66") (name "/SHIFT_UP") (class "Default")
      (node (ref "IC1") (pin "53") (pinfunction "PC12_53") (pintype "passive"))
      (node (ref "IC18") (pin "12") (pinfunction "COLLECTOR_2_12") (pintype "passive"))
      (node (ref "R78") (pin "2") (pintype "passive"))
    )
    (net (code "67") (name "/SHIFT_UP_IN") (class "Default")
      (node (ref "CN1") (pin "2") (pinfunction "2_2") (pintype "passive"))
      (node (ref "R86") (pin "1") (pintype "passive"))
    )
    (net (code "68") (name "/STM_RST") (class "Default")
      (node (ref "C3") (pin "1") (pintype "passive"))
      (node (ref "IC1") (pin "7") (pinfunction "NRST_7") (pintype "input"))
      (node (ref "K1") (pin "1") (pinfunction "1_1") (pintype "passive"))
      (node (ref "R2") (pin "1") (pintype "passive"))
    )
    (net (code "69") (name "/SWCLK") (class "Default")
      (node (ref "IC1") (pin "49") (pinfunction "PA14_49") (pintype "passive"))
      (node (ref "P2") (pin "3") (pinfunction "3_3") (pintype "passive"))
    )
    (net (code "70") (name "/SWDIO") (class "Default")
      (node (ref "IC1") (pin "46") (pinfunction "PA13_46") (pintype "passive"))
      (node (ref "P2") (pin "2") (pinfunction "2_2") (pintype "passive"))
    )
    (net (code "71") (name "/TFT") (class "Default")
      (node (ref "C67") (pin "2") (pintype "passive"))
      (node (ref "CN1") (pin "9") (pinfunction "9_9") (pintype "passive"))
      (node (ref "IC1") (pin "9") (pinfunction "PC1_9") (pintype "passive"))
      (node (ref "R67") (pin "2") (pintype "passive"))
      (node (ref "Z18") (pin "1") (pinfunction "K_1") (pintype "passive"))
    )
    (net (code "72") (name "/TPS") (class "Default")
      (node (ref "CN1") (pin "10") (pinfunction "10_10") (pintype "passive"))
      (node (ref "R66") (pin "1") (pintype "passive"))
    )
    (net (code "73") (name "/TPS_SNS") (class "Default")
      (node (ref "IC1") (pin "11") (pinfunction "PC3_11") (pintype "passive"))
      (node (ref "R66") (pin "2") (pintype "passive"))
      (node (ref "R70") (pin "1") (pintype "passive"))
      (node (ref "Z17") (pin "1") (pinfunction "K_1") (pintype "passive"))
    )
    (net (code "74") (name "/TXD1") (class "Default")
      (node (ref "IC1") (pin "62") (pinfunction "PB9_62") (pintype "passive"))
      (node (ref "IC6") (pin "1") (pinfunction "TXD_1") (pintype "passive"))
    )
    (net (code "75") (name "/TXD2") (class "Default")
      (node (ref "IC1") (pin "58") (pinfunction "PB6_58") (pintype "passive"))
      (node (ref "IC7") (pin "1") (pinfunction "TXD_1") (pintype "passive"))
    )
    (net (code "76") (name "/USB_D+") (class "Default")
      (node (ref "J1") (pin "3") (pinfunction "3_3") (pintype "passive"))
      (node (ref "R14") (pin "1") (pintype "passive"))
      (node (ref "R18") (pin "2") (pintype "passive"))
    )
    (net (code "77") (name "/USB_D-") (class "Default")
      (node (ref "J1") (pin "2") (pinfunction "2_2") (pintype "passive"))
      (node (ref "R16") (pin "2") (pintype "passive"))
    )
    (net (code "78") (name "/VSS_GND") (class "Default")
      (node (ref "CN1") (pin "19") (pinfunction "19_19") (pintype "passive"))
      (node (ref "IC16") (pin "2") (pinfunction "CATHODE_2") (pintype "passive"))
      (node (ref "R82") (pin "2") (pintype "passive"))
    )
    (net (code "79") (name "/VSS_SIG") (class "Default")
      (node (ref "CN1") (pin "7") (pinfunction "7_7") (pintype "passive"))
      (node (ref "R71") (pin "1") (pintype "passive"))
    )
    (net (code "80") (name "/VSS_SNS") (class "Default")
      (node (ref "IC1") (pin "8") (pinfunction "PC0_8") (pintype "passive"))
      (node (ref "IC16") (pin "4") (pinfunction "COLLECTOR_4") (pintype "passive"))
      (node (ref "R69") (pin "2") (pintype "passive"))
    )
    (net (code "81") (name "/V_USB") (class "Default")
      (node (ref "D1") (pin "1") (pintype "passive"))
      (node (ref "J1") (pin "1") (pinfunction "1_1") (pintype "passive"))
      (node (ref "R14") (pin "2") (pintype "passive"))
    )
    (net (code "82") (name "/Voltage_sens") (class "Default")
      (node (ref "IC1") (pin "15") (pinfunction "PA1_15") (pintype "passive"))
      (node (ref "R39") (pin "2") (pintype "passive"))
      (node (ref "R41") (pin "1") (pintype "passive"))
      (node (ref "Z10") (pin "1") (pinfunction "K_1") (pintype "passive"))
    )
    (net (code "83") (name "/led_R") (class "Default")
      (node (ref "IC1") (pin "2") (pinfunction "PC13-RTC_AF1_2") (pintype "passive"))
      (node (ref "R1") (pin "1") (pintype "passive"))
    )
    (net (code "84") (name "/osc_in") (class "Default")
      (node (ref "C2") (pin "2") (pintype "passive"))
      (node (ref "IC1") (pin "5") (pinfunction "PH0-OSC_IN_5") (pintype "input"))
      (node (ref "Y1") (pin "2") (pintype "passive"))
    )
    (net (code "85") (name "/osc_out") (class "Default")
      (node (ref "IC1") (pin "6") (pinfunction "PH1-OSC_OUT_6") (pintype "output"))
      (node (ref "R89") (pin "1") (pintype "passive"))
    )
    (net (code "86") (name "3.3") (class "Default")
      (node (ref "C1") (pin "1") (pintype "passive"))
      (node (ref "C11") (pin "1") (pintype "passive"))
      (node (ref "C12") (pin "2") (pintype "passive"))
      (node (ref "C13") (pin "2") (pintype "passive"))
      (node (ref "C14") (pin "2") (pintype "passive"))
      (node (ref "C16") (pin "2") (pintype "passive"))
      (node (ref "C17") (pin "1") (pintype "passive"))
      (node (ref "C22") (pin "1") (pintype "passive"))
      (node (ref "C27") (pin "1") (pintype "passive"))
      (node (ref "C29") (pin "1") (pintype "passive"))
      (node (ref "C30") (pin "1") (pintype "passive"))
      (node (ref "C38") (pin "1") (pintype "passive"))
      (node (ref "C39") (pin "1") (pintype "passive"))
      (node (ref "C40") (pin "2") (pintype "passive"))
      (node (ref "C41") (pin "2") (pintype "passive"))
      (node (ref "C42") (pin "2") (pintype "passive"))
      (node (ref "C59") (pin "1") (pintype "passive"))
      (node (ref "C60") (pin "1") (pintype "passive"))
      (node (ref "C61") (pin "2") (pintype "passive"))
      (node (ref "C62") (pin "2") (pintype "passive"))
      (node (ref "C8") (pin "1") (pintype "passive"))
      (node (ref "FB1") (pin "1") (pinfunction "1_1") (pintype "passive"))
      (node (ref "IC1") (pin "19") (pinfunction "VDD_1_19") (pintype "power_in"))
      (node (ref "IC1") (pin "32") (pinfunction "VDD_2_32") (pintype "power_in"))
      (node (ref "IC1") (pin "48") (pinfunction "VDD_3_48") (pintype "power_in"))
      (node (ref "IC1") (pin "64") (pinfunction "VDD_4_64") (pintype "power_in"))
      (node (ref "IC10") (pin "5") (pinfunction "VS_5") (pintype "passive"))
      (node (ref "IC11") (pin "5") (pinfunction "VS_5") (pintype "passive"))
      (node (ref "IC13") (pin "5") (pinfunction "VS_5") (pintype "passive"))
      (node (ref "IC14") (pin "5") (pinfunction "VS_5") (pintype "passive"))
      (node (ref "IC15") (pin "2") (pinfunction "VOUT_1_2") (pintype "passive"))
      (node (ref "IC15") (pin "4") (pinfunction "VOUT_2_4") (pintype "passive"))
      (node (ref "IC2") (pin "5") (pinfunction "VS_5") (pintype "passive"))
      (node (ref "IC3") (pin "5") (pinfunction "VS_5") (pintype "passive"))
      (node (ref "IC4") (pin "5") (pinfunction "VS_5") (pintype "passive"))
      (node (ref "IC5") (pin "8") (pinfunction "VCC_8") (pintype "passive"))
      (node (ref "IC6") (pin "5") (pinfunction "VIO_5") (pintype "passive"))
      (node (ref "IC7") (pin "5") (pinfunction "VIO_5") (pintype "passive"))
      (node (ref "IC8") (pin "5") (pinfunction "VS_5") (pintype "passive"))
      (node (ref "IC9") (pin "5") (pinfunction "VS_5") (pintype "passive"))
      (node (ref "LD1") (pin "1") (pinfunction "A_1") (pintype "passive"))
      (node (ref "R11") (pin "1") (pintype "passive"))
      (node (ref "R13") (pin "1") (pintype "passive"))
      (node (ref "R2") (pin "2") (pintype "passive"))
      (node (ref "R58") (pin "2") (pintype "passive"))
      (node (ref "R69") (pin "1") (pintype "passive"))
      (node (ref "R72") (pin "1") (pintype "passive"))
      (node (ref "R73") (pin "1") (pintype "passive"))
      (node (ref "R74") (pin "1") (pintype "passive"))
      (node (ref "R75") (pin "1") (pintype "passive"))
      (node (ref "R76") (pin "1") (pintype "passive"))
      (node (ref "R77") (pin "1") (pintype "passive"))
      (node (ref "R78") (pin "1") (pintype "passive"))
      (node (ref "R79") (pin "1") (pintype "passive"))
      (node (ref "S1") (pin "2") (pinfunction "2_2") (pintype "passive"))
      (node (ref "S1") (pin "4") (pinfunction "4_4") (pintype "passive"))
      (node (ref "Z15") (pin "1") (pinfunction "K_1") (pintype "passive"))
    )
    (net (code "87") (name "GND") (class "Default")
      (node (ref "C1") (pin "2") (pintype "passive"))
      (node (ref "C10") (pin "1") (pintype "passive"))
      (node (ref "C11") (pin "2") (pintype "passive"))
      (node (ref "C12") (pin "1") (pintype "passive"))
      (node (ref "C13") (pin "1") (pintype "passive"))
      (node (ref "C14") (pin "1") (pintype "passive"))
      (node (ref "C15") (pin "2") (pintype "passive"))
      (node (ref "C16") (pin "1") (pintype "passive"))
      (node (ref "C17") (pin "2") (pintype "passive"))
      (node (ref "C2") (pin "1") (pintype "passive"))
      (node (ref "C20") (pin "1") (pintype "passive"))
      (node (ref "C21") (pin "1") (pintype "passive"))
      (node (ref "C22") (pin "2") (pintype "passive"))
      (node (ref "C23") (pin "1") (pintype "passive"))
      (node (ref "C24") (pin "1") (pintype "passive"))
      (node (ref "C25") (pin "1") (pintype "passive"))
      (node (ref "C26") (pin "2") (pintype "passive"))
      (node (ref "C28") (pin "2") (pintype "passive"))
      (node (ref "C29") (pin "2") (pintype "passive"))
      (node (ref "C3") (pin "2") (pintype "passive"))
      (node (ref "C30") (pin "2") (pintype "passive"))
      (node (ref "C31") (pin "1") (pintype "passive"))
      (node (ref "C32") (pin "2") (pintype "passive"))
      (node (ref "C33") (pin "1") (pintype "passive"))
      (node (ref "C34") (pin "1") (pintype "passive"))
      (node (ref "C35") (pin "1") (pintype "passive"))
      (node (ref "C36") (pin "1") (pintype "passive"))
      (node (ref "C37") (pin "2") (pintype "passive"))
      (node (ref "C39") (pin "2") (pintype "passive"))
      (node (ref "C4") (pin "1") (pintype "passive"))
      (node (ref "C40") (pin "1") (pintype "passive"))
      (node (ref "C41") (pin "1") (pintype "passive"))
      (node (ref "C42") (pin "1") (pintype "passive"))
      (node (ref "C43") (pin "2") (pintype "passive"))
      (node (ref "C44") (pin "2") (pinfunction "-_2") (pintype "passive"))
      (node (ref "C45") (pin "2") (pinfunction "-_2") (pintype "passive"))
      (node (ref "C46") (pin "2") (pinfunction "-_2") (pintype "passive"))
      (node (ref "C48") (pin "2") (pintype "passive"))
      (node (ref "C49") (pin "1") (pintype "passive"))
      (node (ref "C5") (pin "1") (pintype "passive"))
      (node (ref "C50") (pin "1") (pintype "passive"))
      (node (ref "C51") (pin "1") (pintype "passive"))
      (node (ref "C52") (pin "1") (pintype "passive"))
      (node (ref "C53") (pin "1") (pintype "passive"))
      (node (ref "C54") (pin "1") (pintype "passive"))
      (node (ref "C55") (pin "2") (pinfunction "-_2") (pintype "passive"))
      (node (ref "C56") (pin "1") (pintype "passive"))
      (node (ref "C57") (pin "1") (pintype "passive"))
      (node (ref "C58") (pin "1") (pintype "passive"))
      (node (ref "C59") (pin "2") (pintype "passive"))
      (node (ref "C6") (pin "1") (pintype "passive"))
      (node (ref "C60") (pin "2") (pintype "passive"))
      (node (ref "C61") (pin "1") (pintype "passive"))
      (node (ref "C62") (pin "1") (pintype "passive"))
      (node (ref "C63") (pin "2") (pintype "passive"))
      (node (ref "C64") (pin "1") (pintype "passive"))
      (node (ref "C65") (pin "1") (pintype "passive"))
      (node (ref "C66") (pin "1") (pintype "passive"))
      (node (ref "C67") (pin "1") (pintype "passive"))
      (node (ref "C7") (pin "1") (pintype "passive"))
      (node (ref "C8") (pin "2") (pintype "passive"))
      (node (ref "C9") (pin "2") (pintype "passive"))
      (node (ref "CN1") (pin "11") (pinfunction "11_11") (pintype "passive"))
      (node (ref "CN1") (pin "20") (pinfunction "20_20") (pintype "passive"))
      (node (ref "CN1") (pin "21") (pinfunction "21_21") (pintype "passive"))
      (node (ref "CN1") (pin "23") (pinfunction "23_23") (pintype "passive"))
      (node (ref "CN2") (pin "1") (pinfunction "1_1") (pintype "passive"))
      (node (ref "CN2") (pin "13") (pinfunction "13_13") (pintype "passive"))
      (node (ref "D7") (pin "2") (pinfunction "A_2") (pintype "passive"))
      (node (ref "D8") (pin "1") (pinfunction "1_1") (pintype "passive"))
      (node (ref "FB2") (pin "1") (pinfunction "1_1") (pintype "passive"))
      (node (ref "IC1") (pin "18") (pinfunction "VSS_1_18") (pintype "power_in"))
      (node (ref "IC1") (pin "63") (pinfunction "VSS_2_63") (pintype "power_in"))
      (node (ref "IC10") (pin "2") (pinfunction "GND_2") (pintype "passive"))
      (node (ref "IC11") (pin "2") (pinfunction "GND_2") (pintype "passive"))
      (node (ref "IC12") (pin "3") (pinfunction "GND_3") (pintype "passive"))
      (node (ref "IC12") (pin "6") (pinfunction "TAB_6") (pintype "passive"))
      (node (ref "IC13") (pin "2") (pinfunction "GND_2") (pintype "passive"))
      (node (ref "IC14") (pin "2") (pinfunction "GND_2") (pintype "passive"))
      (node (ref "IC15") (pin "1") (pinfunction "GND_1") (pintype "passive"))
      (node (ref "IC16") (pin "3") (pinfunction "EMITTER_3") (pintype "passive"))
      (node (ref "IC17") (pin "11") (pinfunction "EMITTER_2_11") (pintype "passive"))
      (node (ref "IC17") (pin "13") (pinfunction "EMITTER_3_13") (pintype "passive"))
      (node (ref "IC17") (pin "15") (pinfunction "EMITTER_4_15") (pintype "passive"))
      (node (ref "IC17") (pin "2") (pinfunction "CATHODE_1_2") (pintype "passive"))
      (node (ref "IC17") (pin "4") (pinfunction "CATHODE_2_4") (pintype "passive"))
      (node (ref "IC17") (pin "6") (pinfunction "CATHODE_3_6") (pintype "passive"))
      (node (ref "IC17") (pin "8") (pinfunction "CATHODE_4_8") (pintype "passive"))
      (node (ref "IC17") (pin "9") (pinfunction "EMITTER_1_9") (pintype "passive"))
      (node (ref "IC18") (pin "11") (pinfunction "EMITTER_2_11") (pintype "passive"))
      (node (ref "IC18") (pin "13") (pinfunction "EMITTER_3_13") (pintype "passive"))
      (node (ref "IC18") (pin "15") (pinfunction "EMITTER_4_15") (pintype "passive"))
      (node (ref "IC18") (pin "2") (pinfunction "CATHODE_1_2") (pintype "passive"))
      (node (ref "IC18") (pin "4") (pinfunction "CATHODE_2_4") (pintype "passive"))
      (node (ref "IC18") (pin "6") (pinfunction "CATHODE_3_6") (pintype "passive"))
      (node (ref "IC18") (pin "8") (pinfunction "CATHODE_4_8") (pintype "passive"))
      (node (ref "IC18") (pin "9") (pinfunction "EMITTER_1_9") (pintype "passive"))
      (node (ref "IC2") (pin "2") (pinfunction "GND_2") (pintype "passive"))
      (node (ref "IC3") (pin "2") (pinfunction "GND_2") (pintype "passive"))
      (node (ref "IC4") (pin "2") (pinfunction "GND_2") (pintype "passive"))
      (node (ref "IC5") (pin "1") (pinfunction "E0_1") (pintype "passive"))
      (node (ref "IC5") (pin "2") (pinfunction "E1_2") (pintype "passive"))
      (node (ref "IC5") (pin "3") (pinfunction "E2_3") (pintype "passive"))
      (node (ref "IC5") (pin "4") (pinfunction "VSS_4") (pintype "passive"))
      (node (ref "IC6") (pin "2") (pinfunction "GND_2") (pintype "passive"))
      (node (ref "IC7") (pin "2") (pinfunction "GND_2") (pintype "passive"))
      (node (ref "IC8") (pin "2") (pinfunction "GND_2") (pintype "passive"))
      (node (ref "IC9") (pin "2") (pinfunction "GND_2") (pintype "passive"))
      (node (ref "J1") (pin "4") (pinfunction "4_4") (pintype "passive"))
      (node (ref "J1") (pin "MH1") (pinfunction "MH1_MH1") (pintype "passive"))
      (node (ref "J1") (pin "MH2") (pinfunction "MH2_MH2") (pintype "passive"))
      (node (ref "K1") (pin "2") (pinfunction "2_2") (pintype "passive"))
      (node (ref "LD13") (pin "2") (pinfunction "K_2") (pintype "passive"))
      (node (ref "P1") (pin "4") (pinfunction "4_4") (pintype "passive"))
      (node (ref "P2") (pin "4") (pinfunction "4_4") (pintype "passive"))
      (node (ref "Q1") (pin "3") (pinfunction "S_3") (pintype "passive"))
      (node (ref "Q10") (pin "3") (pinfunction "C_3") (pintype "passive"))
      (node (ref "Q11") (pin "3") (pinfunction "C_3") (pintype "passive"))
      (node (ref "Q12") (pin "3") (pinfunction "C_3") (pintype "passive"))
      (node (ref "Q13") (pin "3") (pinfunction "S_3") (pintype "passive"))
      (node (ref "Q14") (pin "3") (pinfunction "S_3") (pintype "passive"))
      (node (ref "Q15") (pin "3") (pinfunction "S_3") (pintype "passive"))
      (node (ref "Q16") (pin "3") (pinfunction "S_3") (pintype "passive"))
      (node (ref "Q2") (pin "3") (pinfunction "S_3") (pintype "passive"))
      (node (ref "Q21") (pin "3") (pinfunction "C_3") (pintype "passive"))
      (node (ref "Q22") (pin "3") (pinfunction "C_3") (pintype "passive"))
      (node (ref "Q23") (pin "3") (pinfunction "C_3") (pintype "passive"))
      (node (ref "Q24") (pin "3") (pinfunction "C_3") (pintype "passive"))
      (node (ref "Q25") (pin "3") (pinfunction "S_3") (pintype "passive"))
      (node (ref "Q26") (pin "3") (pinfunction "S_3") (pintype "passive"))
      (node (ref "Q27") (pin "3") (pinfunction "S_3") (pintype "passive"))
      (node (ref "Q3") (pin "3") (pinfunction "S_3") (pintype "passive"))
      (node (ref "Q31") (pin "3") (pinfunction "C_3") (pintype "passive"))
      (node (ref "Q32") (pin "3") (pinfunction "C_3") (pintype "passive"))
      (node (ref "Q33") (pin "3") (pinfunction "C_3") (pintype "passive"))
      (node (ref "Q4") (pin "3") (pinfunction "S_3") (pintype "passive"))
      (node (ref "Q9") (pin "3") (pinfunction "C_3") (pintype "passive"))
      (node (ref "R17") (pin "2") (pintype "passive"))
      (node (ref "R41") (pin "2") (pintype "passive"))
      (node (ref "R49") (pin "2") (pintype "passive"))
      (node (ref "R50") (pin "1") (pintype "passive"))
      (node (ref "R51") (pin "1") (pintype "passive"))
      (node (ref "R68") (pin "2") (pintype "passive"))
      (node (ref "R70") (pin "2") (pintype "passive"))
      (node (ref "R82") (pin "1") (pintype "passive"))
      (node (ref "Z10") (pin "2") (pinfunction "A_2") (pintype "passive"))
      (node (ref "Z11") (pin "2") (pinfunction "A_2") (pintype "passive"))
      (node (ref "Z15") (pin "2") (pinfunction "A_2") (pintype "passive"))
      (node (ref "Z16") (pin "2") (pinfunction "A_2") (pintype "passive"))
      (node (ref "Z17") (pin "2") (pinfunction "A_2") (pintype "passive"))
      (node (ref "Z18") (pin "2") (pinfunction "A_2") (pintype "passive"))
      (node (ref "Z5") (pin "2") (pinfunction "A_2") (pintype "passive"))
    )
    (net (code "88") (name "Net-(C4-Pad2)") (class "Default")
      (node (ref "C4") (pin "2") (pintype "passive"))
      (node (ref "R89") (pin "2") (pintype "passive"))
      (node (ref "Y1") (pin "1") (pintype "passive"))
    )
    (net (code "89") (name "Net-(C20-Pad2)") (class "Default")
      (node (ref "C20") (pin "2") (pintype "passive"))
      (node (ref "R26") (pin "1") (pintype "passive"))
      (node (ref "R27") (pin "2") (pintype "passive"))
    )
    (net (code "90") (name "Net-(C31-Pad2)") (class "Default")
      (node (ref "C31") (pin "2") (pintype "passive"))
      (node (ref "R28") (pin "1") (pintype "passive"))
      (node (ref "R33") (pin "2") (pintype "passive"))
    )
    (net (code "91") (name "Net-(C32-Pad1)") (class "Default")
      (node (ref "C32") (pin "1") (pintype "passive"))
      (node (ref "R30") (pin "2") (pintype "passive"))
    )
    (net (code "92") (name "Net-(D6-A)") (class "Default")
      (node (ref "D6") (pin "2") (pinfunction "A_2") (pintype "passive"))
      (node (ref "F1") (pin "2") (pinfunction "2_2") (pintype "passive"))
    )
    (net (code "93") (name "Net-(D6-K)") (class "Default")
      (node (ref "D6") (pin "1") (pinfunction "K_1") (pintype "passive"))
      (node (ref "D7") (pin "1") (pinfunction "K_1") (pintype "passive"))
      (node (ref "D8") (pin "2") (pinfunction "2_2") (pintype "passive"))
      (node (ref "IC8") (pin "3") (pinfunction "IN+_3") (pintype "passive"))
      (node (ref "R30") (pin "1") (pintype "passive"))
      (node (ref "R35") (pin "2") (pintype "passive"))
      (node (ref "Z5") (pin "1") (pinfunction "K_1") (pintype "passive"))
    )
    (net (code "94") (name "Net-(D13-Pad1)") (class "Default")
      (node (ref "D13") (pin "1") (pintype "passive"))
      (node (ref "P1") (pin "1") (pinfunction "1_1") (pintype "passive"))
    )
    (net (code "95") (name "Net-(D14-Pad1)") (class "Default")
      (node (ref "D14") (pin "1") (pintype "passive"))
      (node (ref "P2") (pin "1") (pinfunction "1_1") (pintype "passive"))
    )
    (net (code "96") (name "Net-(IC1-PA8)") (class "Default")
      (node (ref "IC1") (pin "41") (pinfunction "PA8_41") (pintype "passive"))
      (node (ref "R10") (pin "1") (pintype "passive"))
      (node (ref "R12") (pin "2") (pintype "passive"))
    )
    (net (code "97") (name "Net-(IC1-VCAP_1)") (class "Default")
      (node (ref "C28") (pin "1") (pintype "passive"))
      (node (ref "IC1") (pin "31") (pinfunction "VCAP_1_31") (pintype "passive"))
    )
    (net (code "98") (name "Net-(IC1-VCAP_2)") (class "Default")
      (node (ref "C9") (pin "1") (pintype "passive"))
      (node (ref "IC1") (pin "47") (pinfunction "VCAP_2_47") (pintype "passive"))
    )
    (net (code "99") (name "Net-(IC2-IN-)") (class "Default")
      (node (ref "IC2") (pin "4") (pinfunction "IN-_4") (pintype "passive"))
      (node (ref "Q2") (pin "2") (pinfunction "D_2") (pintype "passive"))
      (node (ref "R7") (pin "1") (pintype "passive"))
    )
    (net (code "100") (name "Net-(IC3-IN-)") (class "Default")
      (node (ref "IC3") (pin "4") (pinfunction "IN-_4") (pintype "passive"))
      (node (ref "Q3") (pin "2") (pinfunction "D_2") (pintype "passive"))
      (node (ref "R8") (pin "1") (pintype "passive"))
    )
    (net (code "101") (name "Net-(IC4-IN-)") (class "Default")
      (node (ref "IC4") (pin "4") (pinfunction "IN-_4") (pintype "passive"))
      (node (ref "Q4") (pin "2") (pinfunction "D_2") (pintype "passive"))
      (node (ref "R9") (pin "1") (pintype "passive"))
    )
    (net (code "102") (name "Net-(IC9-IN-)") (class "Default")
      (node (ref "IC9") (pin "4") (pinfunction "IN-_4") (pintype "passive"))
      (node (ref "Q14") (pin "2") (pinfunction "D_2") (pintype "passive"))
      (node (ref "R36") (pin "1") (pintype "passive"))
    )
    (net (code "103") (name "Net-(IC10-IN-)") (class "Default")
      (node (ref "IC10") (pin "4") (pinfunction "IN-_4") (pintype "passive"))
      (node (ref "Q15") (pin "2") (pinfunction "D_2") (pintype "passive"))
      (node (ref "R37") (pin "1") (pintype "passive"))
    )
    (net (code "104") (name "Net-(IC11-IN-)") (class "Default")
      (node (ref "IC11") (pin "4") (pinfunction "IN-_4") (pintype "passive"))
      (node (ref "Q16") (pin "2") (pinfunction "D_2") (pintype "passive"))
      (node (ref "R38") (pin "1") (pintype "passive"))
    )
    (net (code "105") (name "Net-(IC12-ADJ)") (class "Default")
      (node (ref "IC12") (pin "5") (pinfunction "ADJ_5") (pintype "passive"))
      (node (ref "R51") (pin "2") (pintype "passive"))
      (node (ref "R52") (pin "1") (pintype "passive"))
    )
    (net (code "106") (name "Net-(IC13-IN-)") (class "Default")
      (node (ref "IC13") (pin "4") (pinfunction "IN-_4") (pintype "passive"))
      (node (ref "Q26") (pin "2") (pinfunction "D_2") (pintype "passive"))
      (node (ref "R56") (pin "1") (pintype "passive"))
    )
    (net (code "107") (name "Net-(IC14-IN-)") (class "Default")
      (node (ref "IC14") (pin "4") (pinfunction "IN-_4") (pintype "passive"))
      (node (ref "Q27") (pin "2") (pinfunction "D_2") (pintype "passive"))
      (node (ref "R57") (pin "1") (pintype "passive"))
    )
    (net (code "108") (name "Net-(IC16-ANODE)") (class "Default")
      (node (ref "IC16") (pin "1") (pinfunction "ANODE_1") (pintype "passive"))
      (node (ref "R71") (pin "2") (pintype "passive"))
    )
    (net (code "109") (name "Net-(IC17-ANODE_1)") (class "Default")
      (node (ref "IC17") (pin "1") (pinfunction "ANODE_1_1") (pintype "passive"))
      (node (ref "R80") (pin "2") (pintype "passive"))
    )
    (net (code "110") (name "Net-(IC17-ANODE_2)") (class "Default")
      (node (ref "IC17") (pin "3") (pinfunction "ANODE_2_3") (pintype "passive"))
      (node (ref "R83") (pin "2") (pintype "passive"))
    )
    (net (code "111") (name "Net-(IC17-ANODE_3)") (class "Default")
      (node (ref "IC17") (pin "5") (pinfunction "ANODE_3_5") (pintype "passive"))
      (node (ref "R85") (pin "2") (pintype "passive"))
    )
    (net (code "112") (name "Net-(IC17-ANODE_4)") (class "Default")
      (node (ref "IC17") (pin "7") (pinfunction "ANODE_4_7") (pintype "passive"))
      (node (ref "R87") (pin "2") (pintype "passive"))
    )
    (net (code "113") (name "Net-(IC18-ANODE_1)") (class "Default")
      (node (ref "IC18") (pin "1") (pinfunction "ANODE_1_1") (pintype "passive"))
      (node (ref "R81") (pin "2") (pintype "passive"))
    )
    (net (code "114") (name "Net-(IC18-ANODE_2)") (class "Default")
      (node (ref "IC18") (pin "3") (pinfunction "ANODE_2_3") (pintype "passive"))
      (node (ref "R84") (pin "2") (pintype "passive"))
    )
    (net (code "115") (name "Net-(IC18-ANODE_3)") (class "Default")
      (node (ref "IC18") (pin "5") (pinfunction "ANODE_3_5") (pintype "passive"))
      (node (ref "R86") (pin "2") (pintype "passive"))
    )
    (net (code "116") (name "Net-(IC18-ANODE_4)") (class "Default")
      (node (ref "IC18") (pin "7") (pinfunction "ANODE_4_7") (pintype "passive"))
      (node (ref "R88") (pin "2") (pintype "passive"))
    )
    (net (code "117") (name "Net-(LD1-K)") (class "Default")
      (node (ref "LD1") (pin "2") (pinfunction "K_2") (pintype "passive"))
      (node (ref "R1") (pin "2") (pintype "passive"))
    )
    (net (code "118") (name "Net-(LD2-A)") (class "Default")
      (node (ref "LD2") (pin "1") (pinfunction "A_1") (pintype "passive"))
      (node (ref "R3") (pin "1") (pintype "passive"))
    )
    (net (code "119") (name "Net-(LD3-A)") (class "Default")
      (node (ref "LD3") (pin "1") (pinfunction "A_1") (pintype "passive"))
      (node (ref "R4") (pin "1") (pintype "passive"))
    )
    (net (code "120") (name "Net-(LD4-A)") (class "Default")
      (node (ref "LD4") (pin "1") (pinfunction "A_1") (pintype "passive"))
      (node (ref "R5") (pin "1") (pintype "passive"))
    )
    (net (code "121") (name "Net-(LD5-A)") (class "Default")
      (node (ref "LD5") (pin "1") (pinfunction "A_1") (pintype "passive"))
      (node (ref "R6") (pin "1") (pintype "passive"))
    )
    (net (code "122") (name "Net-(LD6-A)") (class "Default")
      (node (ref "LD6") (pin "1") (pinfunction "A_1") (pintype "passive"))
      (node (ref "R29") (pin "1") (pintype "passive"))
    )
    (net (code "123") (name "Net-(LD7-A)") (class "Default")
      (node (ref "LD7") (pin "1") (pinfunction "A_1") (pintype "passive"))
      (node (ref "R31") (pin "1") (pintype "passive"))
    )
    (net (code "124") (name "Net-(LD8-A)") (class "Default")
      (node (ref "LD8") (pin "1") (pinfunction "A_1") (pintype "passive"))
      (node (ref "R32") (pin "1") (pintype "passive"))
    )
    (net (code "125") (name "Net-(LD9-A)") (class "Default")
      (node (ref "LD9") (pin "1") (pinfunction "A_1") (pintype "passive"))
      (node (ref "R34") (pin "1") (pintype "passive"))
    )
    (net (code "126") (name "Net-(LD10-A)") (class "Default")
      (node (ref "LD10") (pin "1") (pinfunction "A_1") (pintype "passive"))
      (node (ref "R53") (pin "1") (pintype "passive"))
    )
    (net (code "127") (name "Net-(LD11-A)") (class "Default")
      (node (ref "LD11") (pin "1") (pinfunction "A_1") (pintype "passive"))
      (node (ref "R54") (pin "1") (pintype "passive"))
    )
    (net (code "128") (name "Net-(LD12-A)") (class "Default")
      (node (ref "LD12") (pin "1") (pinfunction "A_1") (pintype "passive"))
      (node (ref "R55") (pin "1") (pintype "passive"))
    )
    (net (code "129") (name "Net-(LD13-A)") (class "Default")
      (node (ref "LD13") (pin "1") (pinfunction "A_1") (pintype "passive"))
      (node (ref "R58") (pin "1") (pintype "passive"))
    )
    (net (code "130") (name "Net-(Q1-G)") (class "Default")
      (node (ref "Q1") (pin "1") (pinfunction "G_1") (pintype "passive"))
      (node (ref "R15") (pin "2") (pintype "passive"))
    )
    (net (code "131") (name "Net-(Q2-G)") (class "Default")
      (node (ref "Q2") (pin "1") (pinfunction "G_1") (pintype "passive"))
      (node (ref "R19") (pin "2") (pintype "passive"))
    )
    (net (code "132") (name "Net-(Q3-G)") (class "Default")
      (node (ref "Q3") (pin "1") (pinfunction "G_1") (pintype "passive"))
      (node (ref "R20") (pin "2") (pintype "passive"))
    )
    (net (code "133") (name "Net-(Q4-G)") (class "Default")
      (node (ref "Q4") (pin "1") (pinfunction "G_1") (pintype "passive"))
      (node (ref "R21") (pin "2") (pintype "passive"))
    )
    (net (code "134") (name "Net-(Q5-B)") (class "Default")
      (node (ref "D2") (pin "1") (pintype "passive"))
      (node (ref "Q5") (pin "1") (pinfunction "B_1") (pintype "bidirectional"))
      (node (ref "Q9") (pin "1") (pinfunction "B_1") (pintype "passive"))
      (node (ref "R22") (pin "1") (pintype "passive"))
    )
    (net (code "135") (name "Net-(Q5-E)") (class "Default")
      (node (ref "Q5") (pin "2") (pinfunction "E_2") (pintype "bidirectional"))
      (node (ref "Q9") (pin "2") (pinfunction "E_2") (pintype "passive"))
      (node (ref "R15") (pin "1") (pintype "passive"))
    )
    (net (code "136") (name "Net-(Q10-B)") (class "Default")
      (node (ref "D3") (pin "1") (pintype "passive"))
      (node (ref "Q10") (pin "1") (pinfunction "B_1") (pintype "passive"))
      (node (ref "Q6") (pin "1") (pinfunction "B_1") (pintype "bidirectional"))
      (node (ref "R23") (pin "1") (pintype "passive"))
    )
    (net (code "137") (name "Net-(Q10-E)") (class "Default")
      (node (ref "Q10") (pin "2") (pinfunction "E_2") (pintype "passive"))
      (node (ref "Q6") (pin "2") (pinfunction "E_2") (pintype "bidirectional"))
      (node (ref "R19") (pin "1") (pintype "passive"))
    )
    (net (code "138") (name "Net-(Q11-B)") (class "Default")
      (node (ref "D4") (pin "1") (pintype "passive"))
      (node (ref "Q11") (pin "1") (pinfunction "B_1") (pintype "passive"))
      (node (ref "Q7") (pin "1") (pinfunction "B_1") (pintype "bidirectional"))
      (node (ref "R24") (pin "1") (pintype "passive"))
    )
    (net (code "139") (name "Net-(Q11-E)") (class "Default")
      (node (ref "Q11") (pin "2") (pinfunction "E_2") (pintype "passive"))
      (node (ref "Q7") (pin "2") (pinfunction "E_2") (pintype "bidirectional"))
      (node (ref "R20") (pin "1") (pintype "passive"))
    )
    (net (code "140") (name "Net-(Q12-B)") (class "Default")
      (node (ref "D5") (pin "1") (pintype "passive"))
      (node (ref "Q12") (pin "1") (pinfunction "B_1") (pintype "passive"))
      (node (ref "Q8") (pin "1") (pinfunction "B_1") (pintype "bidirectional"))
      (node (ref "R25") (pin "1") (pintype "passive"))
    )
    (net (code "141") (name "Net-(Q12-E)") (class "Default")
      (node (ref "Q12") (pin "2") (pinfunction "E_2") (pintype "passive"))
      (node (ref "Q8") (pin "2") (pinfunction "E_2") (pintype "bidirectional"))
      (node (ref "R21") (pin "1") (pintype "passive"))
    )
    (net (code "142") (name "Net-(Q13-G)") (class "Default")
      (node (ref "Q13") (pin "1") (pinfunction "G_1") (pintype "passive"))
      (node (ref "R40") (pin "2") (pintype "passive"))
    )
    (net (code "143") (name "Net-(Q14-G)") (class "Default")
      (node (ref "Q14") (pin "1") (pinfunction "G_1") (pintype "passive"))
      (node (ref "R42") (pin "2") (pintype "passive"))
    )
    (net (code "144") (name "Net-(Q15-G)") (class "Default")
      (node (ref "Q15") (pin "1") (pinfunction "G_1") (pintype "passive"))
      (node (ref "R43") (pin "2") (pintype "passive"))
    )
    (net (code "145") (name "Net-(Q16-G)") (class "Default")
      (node (ref "Q16") (pin "1") (pinfunction "G_1") (pintype "passive"))
      (node (ref "R44") (pin "2") (pintype "passive"))
    )
    (net (code "146") (name "Net-(Q17-B)") (class "Default")
      (node (ref "D9") (pin "1") (pintype "passive"))
      (node (ref "Q17") (pin "1") (pinfunction "B_1") (pintype "bidirectional"))
      (node (ref "Q21") (pin "1") (pinfunction "B_1") (pintype "passive"))
      (node (ref "R45") (pin "1") (pintype "passive"))
    )
    (net (code "147") (name "Net-(Q17-E)") (class "Default")
      (node (ref "Q17") (pin "2") (pinfunction "E_2") (pintype "bidirectional"))
      (node (ref "Q21") (pin "2") (pinfunction "E_2") (pintype "passive"))
      (node (ref "R40") (pin "1") (pintype "passive"))
    )
    (net (code "148") (name "Net-(Q18-B)") (class "Default")
      (node (ref "D10") (pin "1") (pintype "passive"))
      (node (ref "Q18") (pin "1") (pinfunction "B_1") (pintype "bidirectional"))
      (node (ref "Q22") (pin "1") (pinfunction "B_1") (pintype "passive"))
      (node (ref "R46") (pin "1") (pintype "passive"))
    )
    (net (code "149") (name "Net-(Q18-E)") (class "Default")
      (node (ref "Q18") (pin "2") (pinfunction "E_2") (pintype "bidirectional"))
      (node (ref "Q22") (pin "2") (pinfunction "E_2") (pintype "passive"))
      (node (ref "R42") (pin "1") (pintype "passive"))
    )
    (net (code "150") (name "Net-(Q19-B)") (class "Default")
      (node (ref "D11") (pin "1") (pintype "passive"))
      (node (ref "Q19") (pin "1") (pinfunction "B_1") (pintype "bidirectional"))
      (node (ref "Q23") (pin "1") (pinfunction "B_1") (pintype "passive"))
      (node (ref "R47") (pin "1") (pintype "passive"))
    )
    (net (code "151") (name "Net-(Q19-E)") (class "Default")
      (node (ref "Q19") (pin "2") (pinfunction "E_2") (pintype "bidirectional"))
      (node (ref "Q23") (pin "2") (pinfunction "E_2") (pintype "passive"))
      (node (ref "R43") (pin "1") (pintype "passive"))
    )
    (net (code "152") (name "Net-(Q20-B)") (class "Default")
      (node (ref "D12") (pin "1") (pintype "passive"))
      (node (ref "Q20") (pin "1") (pinfunction "B_1") (pintype "bidirectional"))
      (node (ref "Q24") (pin "1") (pinfunction "B_1") (pintype "passive"))
      (node (ref "R48") (pin "1") (pintype "passive"))
    )
    (net (code "153") (name "Net-(Q20-E)") (class "Default")
      (node (ref "Q20") (pin "2") (pinfunction "E_2") (pintype "bidirectional"))
      (node (ref "Q24") (pin "2") (pinfunction "E_2") (pintype "passive"))
      (node (ref "R44") (pin "1") (pintype "passive"))
    )
    (net (code "154") (name "Net-(Q25-G)") (class "Default")
      (node (ref "Q25") (pin "1") (pinfunction "G_1") (pintype "passive"))
      (node (ref "R59") (pin "2") (pintype "passive"))
    )
    (net (code "155") (name "Net-(Q26-G)") (class "Default")
      (node (ref "Q26") (pin "1") (pinfunction "G_1") (pintype "passive"))
      (node (ref "R60") (pin "2") (pintype "passive"))
    )
    (net (code "156") (name "Net-(Q27-G)") (class "Default")
      (node (ref "Q27") (pin "1") (pinfunction "G_1") (pintype "passive"))
      (node (ref "R61") (pin "2") (pintype "passive"))
    )
    (net (code "157") (name "Net-(Q28-B)") (class "Default")
      (node (ref "D15") (pin "1") (pintype "passive"))
      (node (ref "Q28") (pin "1") (pinfunction "B_1") (pintype "bidirectional"))
      (node (ref "Q31") (pin "1") (pinfunction "B_1") (pintype "passive"))
      (node (ref "R62") (pin "1") (pintype "passive"))
    )
    (net (code "158") (name "Net-(Q28-E)") (class "Default")
      (node (ref "Q28") (pin "2") (pinfunction "E_2") (pintype "bidirectional"))
      (node (ref "Q31") (pin "2") (pinfunction "E_2") (pintype "passive"))
      (node (ref "R59") (pin "1") (pintype "passive"))
    )
    (net (code "159") (name "Net-(Q29-B)") (class "Default")
      (node (ref "D16") (pin "1") (pintype "passive"))
      (node (ref "Q29") (pin "1") (pinfunction "B_1") (pintype "bidirectional"))
      (node (ref "Q32") (pin "1") (pinfunction "B_1") (pintype "passive"))
      (node (ref "R63") (pin "1") (pintype "passive"))
    )
    (net (code "160") (name "Net-(Q29-E)") (class "Default")
      (node (ref "Q29") (pin "2") (pinfunction "E_2") (pintype "bidirectional"))
      (node (ref "Q32") (pin "2") (pinfunction "E_2") (pintype "passive"))
      (node (ref "R60") (pin "1") (pintype "passive"))
    )
    (net (code "161") (name "Net-(Q30-B)") (class "Default")
      (node (ref "D17") (pin "1") (pintype "passive"))
      (node (ref "Q30") (pin "1") (pinfunction "B_1") (pintype "bidirectional"))
      (node (ref "Q33") (pin "1") (pinfunction "B_1") (pintype "passive"))
      (node (ref "R64") (pin "1") (pintype "passive"))
    )
    (net (code "162") (name "Net-(Q30-E)") (class "Default")
      (node (ref "Q30") (pin "2") (pinfunction "E_2") (pintype "bidirectional"))
      (node (ref "Q33") (pin "2") (pinfunction "E_2") (pintype "passive"))
      (node (ref "R61") (pin "1") (pintype "passive"))
    )
    (net (code "163") (name "VCC") (class "Default")
      (node (ref "C43") (pin "1") (pintype "passive"))
      (node (ref "C44") (pin "1") (pinfunction "+_1") (pintype "passive"))
      (node (ref "C53") (pin "2") (pintype "passive"))
      (node (ref "CN1") (pin "8") (pinfunction "8_8") (pintype "passive"))
      (node (ref "IC12") (pin "1") (pinfunction "EN_1") (pintype "passive"))
      (node (ref "IC12") (pin "2") (pinfunction "IN_2") (pintype "passive"))
      (node (ref "IC8") (pin "4") (pinfunction "IN-_4") (pintype "passive"))
      (node (ref "R35") (pin "1") (pintype "passive"))
      (node (ref "R39") (pin "1") (pintype "passive"))
    )
    (net (code "164") (name "VDDA") (class "Default")
      (node (ref "C18") (pin "1") (pintype "passive"))
      (node (ref "C19") (pin "2") (pintype "passive"))
      (node (ref "FB1") (pin "2") (pinfunction "2_2") (pintype "passive"))
      (node (ref "IC1") (pin "13") (pinfunction "VDDA_13") (pintype "power_in"))
    )
    (net (code "165") (name "VSSA") (class "Default")
      (node (ref "C18") (pin "2") (pintype "passive"))
      (node (ref "C19") (pin "1") (pintype "passive"))
      (node (ref "FB2") (pin "2") (pinfunction "2_2") (pintype "passive"))
      (node (ref "IC1") (pin "12") (pinfunction "VSSA_12") (pintype "power_in"))
    )
    (net (code "166") (name "V_SELONOID") (class "Default")
      (node (ref "C21") (pin "2") (pintype "passive"))
      (node (ref "C23") (pin "2") (pintype "passive"))
      (node (ref "C24") (pin "2") (pintype "passive"))
      (node (ref "C25") (pin "2") (pintype "passive"))
      (node (ref "C45") (pin "1") (pinfunction "+_1") (pintype "passive"))
      (node (ref "C46") (pin "1") (pinfunction "+_1") (pintype "passive"))
      (node (ref "C48") (pin "1") (pintype "passive"))
      (node (ref "C49") (pin "2") (pintype "passive"))
      (node (ref "C50") (pin "2") (pintype "passive"))
      (node (ref "C51") (pin "2") (pintype "passive"))
      (node (ref "C52") (pin "2") (pintype "passive"))
      (node (ref "C64") (pin "2") (pintype "passive"))
      (node (ref "C65") (pin "2") (pintype "passive"))
      (node (ref "C66") (pin "2") (pintype "passive"))
      (node (ref "CN2") (pin "10") (pinfunction "10_10") (pintype "passive"))
      (node (ref "CN2") (pin "11") (pinfunction "11_11") (pintype "passive"))
      (node (ref "CN2") (pin "12") (pinfunction "12_12") (pintype "passive"))
      (node (ref "CN2") (pin "2") (pinfunction "2_2") (pintype "passive"))
      (node (ref "CN2") (pin "3") (pinfunction "3_3") (pintype "passive"))
      (node (ref "CN2") (pin "4") (pinfunction "4_4") (pintype "passive"))
      (node (ref "CN2") (pin "5") (pinfunction "5_5") (pintype "passive"))
      (node (ref "CN2") (pin "6") (pinfunction "6_6") (pintype "passive"))
      (node (ref "CN2") (pin "7") (pinfunction "7_7") (pintype "passive"))
      (node (ref "CN2") (pin "8") (pinfunction "8_8") (pintype "passive"))
      (node (ref "CN2") (pin "9") (pinfunction "9_9") (pintype "passive"))
      (node (ref "D10") (pin "2") (pintype "passive"))
      (node (ref "D11") (pin "2") (pintype "passive"))
      (node (ref "D12") (pin "2") (pintype "passive"))
      (node (ref "D15") (pin "2") (pintype "passive"))
      (node (ref "D16") (pin "2") (pintype "passive"))
      (node (ref "D17") (pin "2") (pintype "passive"))
      (node (ref "D2") (pin "2") (pintype "passive"))
      (node (ref "D3") (pin "2") (pintype "passive"))
      (node (ref "D4") (pin "2") (pintype "passive"))
      (node (ref "D5") (pin "2") (pintype "passive"))
      (node (ref "D9") (pin "2") (pintype "passive"))
      (node (ref "F1") (pin "1") (pinfunction "1_1") (pintype "passive"))
      (node (ref "Q17") (pin "3") (pinfunction "C_3") (pintype "bidirectional"))
      (node (ref "Q18") (pin "3") (pinfunction "C_3") (pintype "bidirectional"))
      (node (ref "Q19") (pin "3") (pinfunction "C_3") (pintype "bidirectional"))
      (node (ref "Q20") (pin "3") (pinfunction "C_3") (pintype "bidirectional"))
      (node (ref "Q28") (pin "3") (pinfunction "C_3") (pintype "bidirectional"))
      (node (ref "Q29") (pin "3") (pinfunction "C_3") (pintype "bidirectional"))
      (node (ref "Q30") (pin "3") (pinfunction "C_3") (pintype "bidirectional"))
      (node (ref "Q5") (pin "3") (pinfunction "C_3") (pintype "bidirectional"))
      (node (ref "Q6") (pin "3") (pinfunction "C_3") (pintype "bidirectional"))
      (node (ref "Q7") (pin "3") (pinfunction "C_3") (pintype "bidirectional"))
      (node (ref "Q8") (pin "3") (pinfunction "C_3") (pintype "bidirectional"))
      (node (ref "R29") (pin "2") (pintype "passive"))
      (node (ref "R3") (pin "2") (pintype "passive"))
      (node (ref "R31") (pin "2") (pintype "passive"))
      (node (ref "R32") (pin "2") (pintype "passive"))
      (node (ref "R34") (pin "2") (pintype "passive"))
      (node (ref "R4") (pin "2") (pintype "passive"))
      (node (ref "R5") (pin "2") (pintype "passive"))
      (node (ref "R53") (pin "2") (pintype "passive"))
      (node (ref "R54") (pin "2") (pintype "passive"))
      (node (ref "R55") (pin "2") (pintype "passive"))
      (node (ref "R6") (pin "2") (pintype "passive"))
      (node (ref "Z1") (pin "1") (pinfunction "K_1") (pintype "passive"))
      (node (ref "Z12") (pin "1") (pinfunction "K_1") (pintype "passive"))
      (node (ref "Z13") (pin "1") (pinfunction "K_1") (pintype "passive"))
      (node (ref "Z14") (pin "1") (pinfunction "K_1") (pintype "passive"))
      (node (ref "Z2") (pin "1") (pinfunction "K_1") (pintype "passive"))
      (node (ref "Z3") (pin "1") (pinfunction "K_1") (pintype "passive"))
      (node (ref "Z4") (pin "1") (pinfunction "K_1") (pintype "passive"))
      (node (ref "Z6") (pin "1") (pinfunction "K_1") (pintype "passive"))
      (node (ref "Z7") (pin "1") (pinfunction "K_1") (pintype "passive"))
      (node (ref "Z8") (pin "1") (pinfunction "K_1") (pintype "passive"))
      (node (ref "Z9") (pin "1") (pinfunction "K_1") (pintype "passive"))
    )
    (net (code "167") (name "unconnected-(IC1-VBAT-Pad1)") (class "Default")
      (node (ref "IC1") (pin "1") (pinfunction "VBAT_1") (pintype "passive+no_connect"))
    )
  )
)
